# as14120_x31_fpga_power_conf.net
KiCad netlist of a schematic drawn in Altium Designer
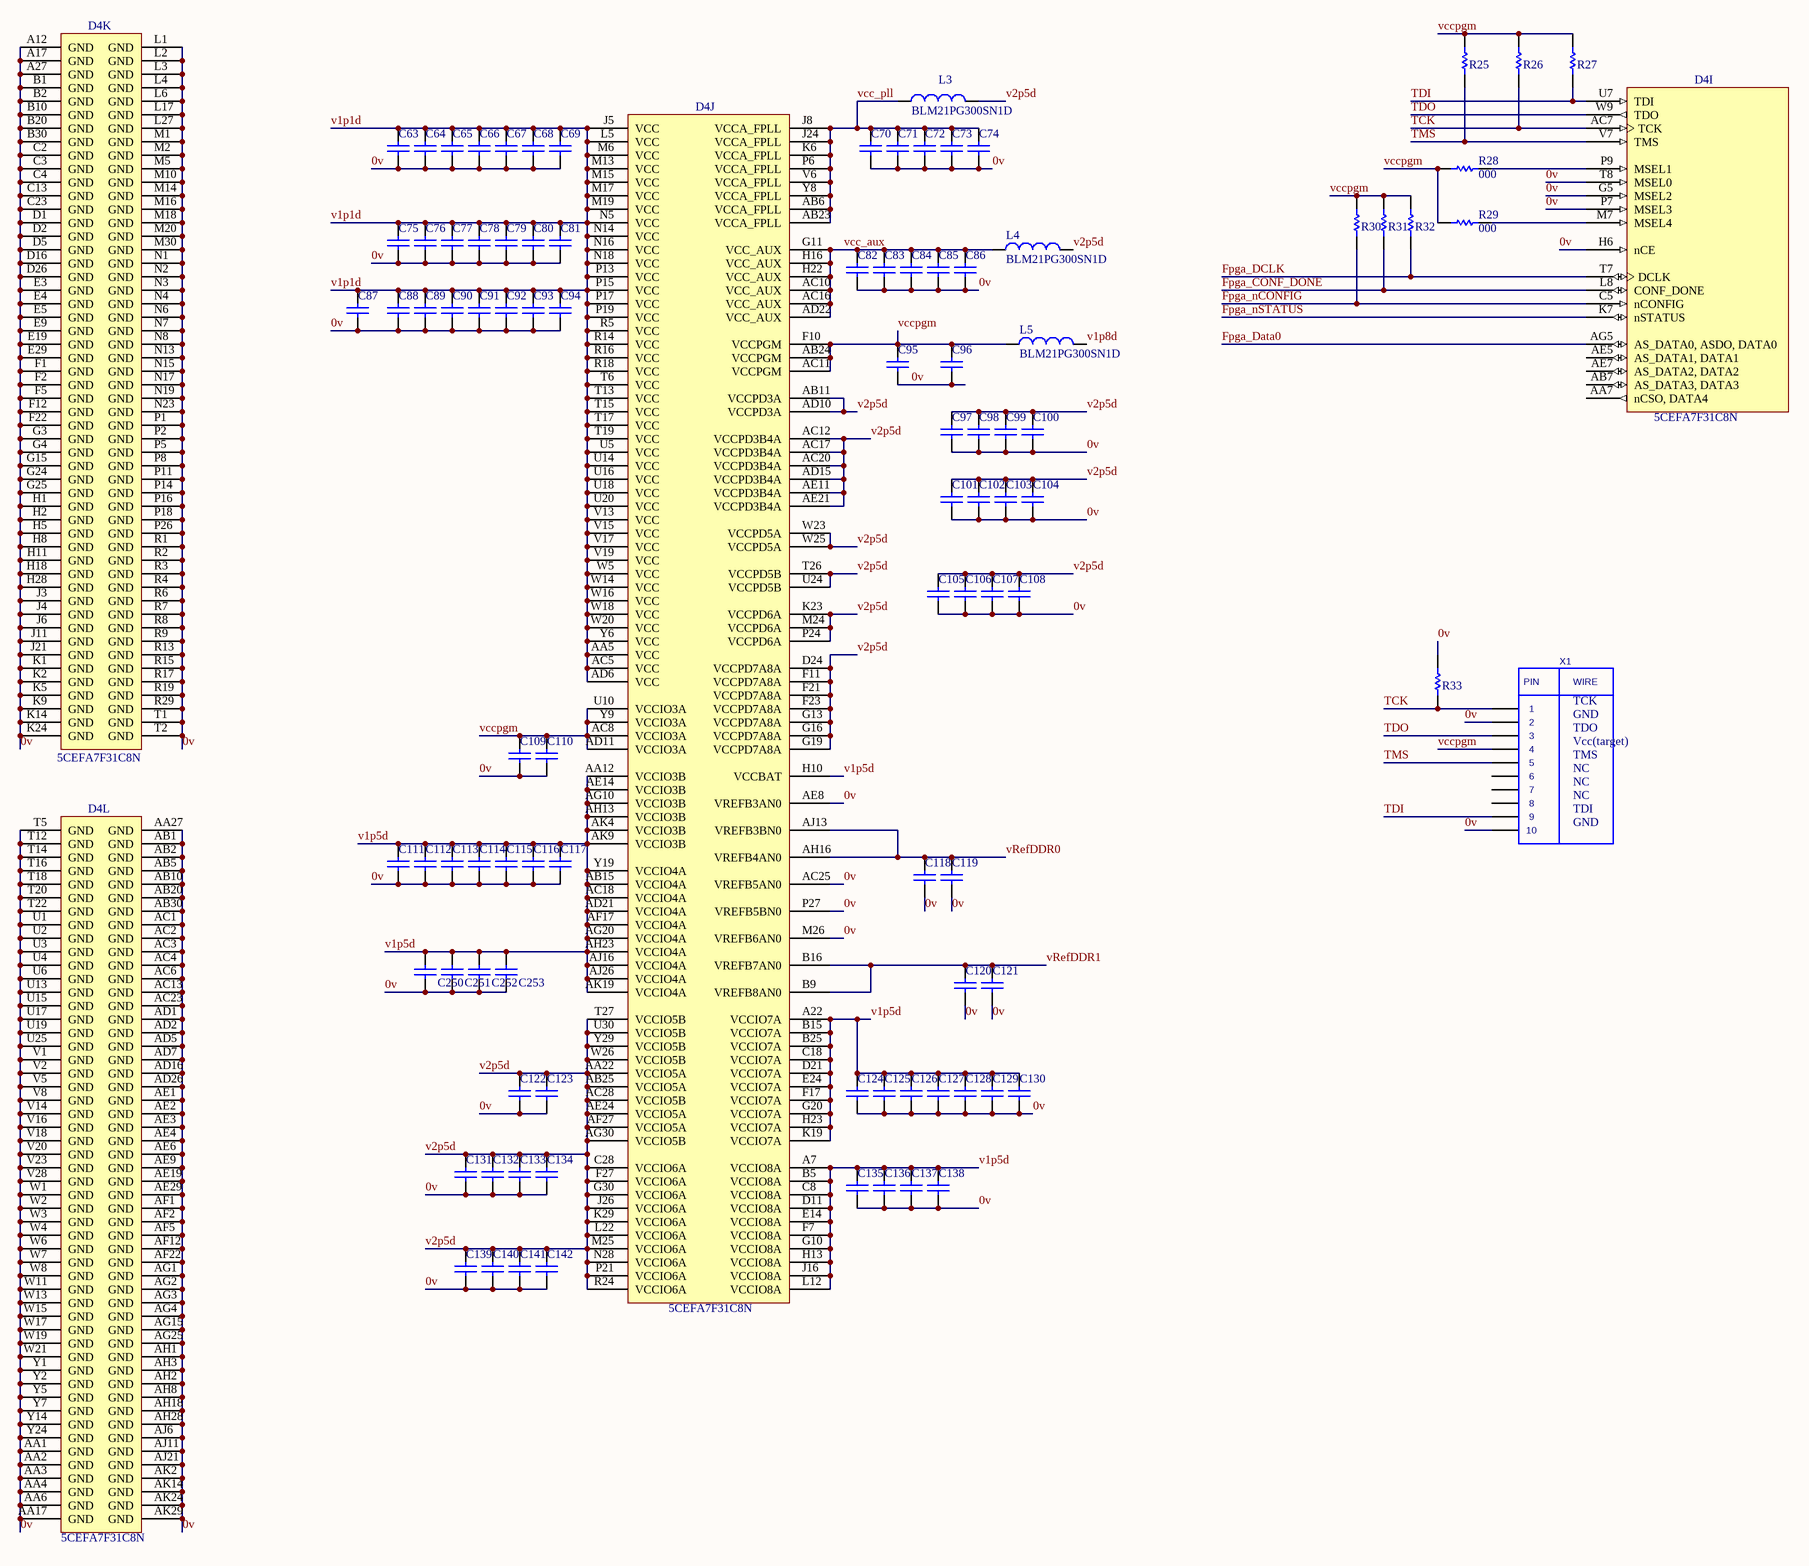
[diagram p0: as14120_x31_fpga_power_conf.SchDoc]

(export (version "E")
  (design (tool "Eeschema 10.0.6"))
  (components
    (comp (ref "C63")
      (value "CAP 1uF 10V 0402(1005)")
      (footprint "CAPC0402(1005)60_M")
      (description "CAP 1uF 10V ±20% 0402 (1005 Metric) Thickness 0.6mm SMD")
      (fields (field (name "TOLERANCE") "±20%"))
      (libsource (lib "as14120") (part "CAP_0402"))
    )
    (comp (ref "C64")
      (value "CAP 1uF 10V 0402(1005)")
      (footprint "CAPC0402(1005)60_M")
      (description "CAP 1uF 10V ±20% 0402 (1005 Metric) Thickness 0.6mm SMD")
      (fields (field (name "TOLERANCE") "±20%"))
      (libsource (lib "as14120") (part "CAP_0402"))
    )
    (comp (ref "C65")
      (value "CAP 1uF 10V 0402(1005)")
      (footprint "CAPC0402(1005)60_M")
      (description "CAP 1uF 10V ±20% 0402 (1005 Metric) Thickness 0.6mm SMD")
      (fields (field (name "TOLERANCE") "±20%"))
      (libsource (lib "as14120") (part "CAP_0402"))
    )
    (comp (ref "C66")
      (value "CAP 1uF 10V 0402(1005)")
      (footprint "CAPC0402(1005)60_M")
      (description "CAP 1uF 10V ±20% 0402 (1005 Metric) Thickness 0.6mm SMD")
      (fields (field (name "TOLERANCE") "±20%"))
      (libsource (lib "as14120") (part "CAP_0402"))
    )
    (comp (ref "C67")
      (value "CAP 1uF 10V 0402(1005)")
      (footprint "CAPC0402(1005)60_M")
      (description "CAP 1uF 10V ±20% 0402 (1005 Metric) Thickness 0.6mm SMD")
      (fields (field (name "TOLERANCE") "±20%"))
      (libsource (lib "as14120") (part "CAP_0402"))
    )
    (comp (ref "C68")
      (value "CAP 1uF 10V 0402(1005)")
      (footprint "CAPC0402(1005)60_M")
      (description "CAP 1uF 10V ±20% 0402 (1005 Metric) Thickness 0.6mm SMD")
      (fields (field (name "TOLERANCE") "±20%"))
      (libsource (lib "as14120") (part "CAP_0402"))
    )
    (comp (ref "C69")
      (value "CAP 1uF 10V 0402(1005)")
      (footprint "CAPC0402(1005)60_M")
      (description "CAP 1uF 10V ±20% 0402 (1005 Metric) Thickness 0.6mm SMD")
      (fields (field (name "TOLERANCE") "±20%"))
      (libsource (lib "as14120") (part "CAP_0402"))
    )
    (comp (ref "C70")
      (value "CAP 1uF 10V 0402(1005)")
      (footprint "CAPC0402(1005)60_M")
      (description "CAP 1uF 10V ±20% 0402 (1005 Metric) Thickness 0.6mm SMD")
      (fields (field (name "TOLERANCE") "±20%"))
      (libsource (lib "as14120") (part "CAP_0402"))
    )
    (comp (ref "C71")
      (value "CAP 1uF 10V 0402(1005)")
      (footprint "CAPC0402(1005)60_M")
      (description "CAP 1uF 10V ±20% 0402 (1005 Metric) Thickness 0.6mm SMD")
      (fields (field (name "TOLERANCE") "±20%"))
      (libsource (lib "as14120") (part "CAP_0402"))
    )
    (comp (ref "C72")
      (value "CAP 1uF 10V 0402(1005)")
      (footprint "CAPC0402(1005)60_M")
      (description "CAP 1uF 10V ±20% 0402 (1005 Metric) Thickness 0.6mm SMD")
      (fields (field (name "TOLERANCE") "±20%"))
      (libsource (lib "as14120") (part "CAP_0402"))
    )
    (comp (ref "C73")
      (value "CAP 1uF 10V 0402(1005)")
      (footprint "CAPC0402(1005)60_M")
      (description "CAP 1uF 10V ±20% 0402 (1005 Metric) Thickness 0.6mm SMD")
      (fields (field (name "TOLERANCE") "±20%"))
      (libsource (lib "as14120") (part "CAP_0402"))
    )
    (comp (ref "C74")
      (value "CAP 1uF 10V 0402(1005)")
      (footprint "CAPC0402(1005)60_M")
      (description "CAP 1uF 10V ±20% 0402 (1005 Metric) Thickness 0.6mm SMD")
      (fields (field (name "TOLERANCE") "±20%"))
      (libsource (lib "as14120") (part "CAP_0402"))
    )
    (comp (ref "C75")
      (value "CAP 1uF 10V 0402(1005)")
      (footprint "CAPC0402(1005)60_M")
      (description "CAP 1uF 10V ±20% 0402 (1005 Metric) Thickness 0.6mm SMD")
      (fields (field (name "TOLERANCE") "±20%"))
      (libsource (lib "as14120") (part "CAP_0402"))
    )
    (comp (ref "C76")
      (value "CAP 1uF 10V 0402(1005)")
      (footprint "CAPC0402(1005)60_M")
      (description "CAP 1uF 10V ±20% 0402 (1005 Metric) Thickness 0.6mm SMD")
      (fields (field (name "TOLERANCE") "±20%"))
      (libsource (lib "as14120") (part "CAP_0402"))
    )
    (comp (ref "C77")
      (value "CAP 1uF 10V 0402(1005)")
      (footprint "CAPC0402(1005)60_M")
      (description "CAP 1uF 10V ±20% 0402 (1005 Metric) Thickness 0.6mm SMD")
      (fields (field (name "TOLERANCE") "±20%"))
      (libsource (lib "as14120") (part "CAP_0402"))
    )
    (comp (ref "C78")
      (value "CAP 1uF 10V 0402(1005)")
      (footprint "CAPC0402(1005)60_M")
      (description "CAP 1uF 10V ±20% 0402 (1005 Metric) Thickness 0.6mm SMD")
      (fields (field (name "TOLERANCE") "±20%"))
      (libsource (lib "as14120") (part "CAP_0402"))
    )
    (comp (ref "C79")
      (value "CAP 1uF 10V 0402(1005)")
      (footprint "CAPC0402(1005)60_M")
      (description "CAP 1uF 10V ±20% 0402 (1005 Metric) Thickness 0.6mm SMD")
      (fields (field (name "TOLERANCE") "±20%"))
      (libsource (lib "as14120") (part "CAP_0402"))
    )
    (comp (ref "C80")
      (value "CAP 1uF 10V 0402(1005)")
      (footprint "CAPC0402(1005)60_M")
      (description "CAP 1uF 10V ±20% 0402 (1005 Metric) Thickness 0.6mm SMD")
      (fields (field (name "TOLERANCE") "±20%"))
      (libsource (lib "as14120") (part "CAP_0402"))
    )
    (comp (ref "C81")
      (value "CAP 1uF 10V 0402(1005)")
      (footprint "CAPC0402(1005)60_M")
      (description "CAP 1uF 10V ±20% 0402 (1005 Metric) Thickness 0.6mm SMD")
      (fields (field (name "TOLERANCE") "±20%"))
      (libsource (lib "as14120") (part "CAP_0402"))
    )
    (comp (ref "C82")
      (value "CAP 1uF 10V 0402(1005)")
      (footprint "CAPC0402(1005)60_M")
      (description "CAP 1uF 10V ±20% 0402 (1005 Metric) Thickness 0.6mm SMD")
      (fields (field (name "TOLERANCE") "±20%"))
      (libsource (lib "as14120") (part "CAP_0402"))
    )
    (comp (ref "C83")
      (value "CAP 1uF 10V 0402(1005)")
      (footprint "CAPC0402(1005)60_M")
      (description "CAP 1uF 10V ±20% 0402 (1005 Metric) Thickness 0.6mm SMD")
      (fields (field (name "TOLERANCE") "±20%"))
      (libsource (lib "as14120") (part "CAP_0402"))
    )
    (comp (ref "C84")
      (value "CAP 1uF 10V 0402(1005)")
      (footprint "CAPC0402(1005)60_M")
      (description "CAP 1uF 10V ±20% 0402 (1005 Metric) Thickness 0.6mm SMD")
      (fields (field (name "TOLERANCE") "±20%"))
      (libsource (lib "as14120") (part "CAP_0402"))
    )
    (comp (ref "C85")
      (value "CAP 1uF 10V 0402(1005)")
      (footprint "CAPC0402(1005)60_M")
      (description "CAP 1uF 10V ±20% 0402 (1005 Metric) Thickness 0.6mm SMD")
      (fields (field (name "TOLERANCE") "±20%"))
      (libsource (lib "as14120") (part "CAP_0402"))
    )
    (comp (ref "C86")
      (value "CAP 1uF 10V 0402(1005)")
      (footprint "CAPC0402(1005)60_M")
      (description "CAP 1uF 10V ±20% 0402 (1005 Metric) Thickness 0.6mm SMD")
      (fields (field (name "TOLERANCE") "±20%"))
      (libsource (lib "as14120") (part "CAP_0402"))
    )
    (comp (ref "C87")
      (value "CAP 1uF 10V 0402(1005)")
      (footprint "CAPC0402(1005)60_M")
      (description "CAP 1uF 10V ±20% 0402 (1005 Metric) Thickness 0.6mm SMD")
      (fields (field (name "TOLERANCE") "±20%"))
      (libsource (lib "as14120") (part "CAP_0402"))
    )
    (comp (ref "C88")
      (value "CAP 1uF 10V 0402(1005)")
      (footprint "CAPC0402(1005)60_M")
      (description "CAP 1uF 10V ±20% 0402 (1005 Metric) Thickness 0.6mm SMD")
      (fields (field (name "TOLERANCE") "±20%"))
      (libsource (lib "as14120") (part "CAP_0402"))
    )
    (comp (ref "C89")
      (value "CAP 1uF 10V 0402(1005)")
      (footprint "CAPC0402(1005)60_M")
      (description "CAP 1uF 10V ±20% 0402 (1005 Metric) Thickness 0.6mm SMD")
      (fields (field (name "TOLERANCE") "±20%"))
      (libsource (lib "as14120") (part "CAP_0402"))
    )
    (comp (ref "C90")
      (value "CAP 1uF 10V 0402(1005)")
      (footprint "CAPC0402(1005)60_M")
      (description "CAP 1uF 10V ±20% 0402 (1005 Metric) Thickness 0.6mm SMD")
      (fields (field (name "TOLERANCE") "±20%"))
      (libsource (lib "as14120") (part "CAP_0402"))
    )
    (comp (ref "C91")
      (value "CAP 1uF 10V 0402(1005)")
      (footprint "CAPC0402(1005)60_M")
      (description "CAP 1uF 10V ±20% 0402 (1005 Metric) Thickness 0.6mm SMD")
      (fields (field (name "TOLERANCE") "±20%"))
      (libsource (lib "as14120") (part "CAP_0402"))
    )
    (comp (ref "C92")
      (value "CAP 1uF 10V 0402(1005)")
      (footprint "CAPC0402(1005)60_M")
      (description "CAP 1uF 10V ±20% 0402 (1005 Metric) Thickness 0.6mm SMD")
      (fields (field (name "TOLERANCE") "±20%"))
      (libsource (lib "as14120") (part "CAP_0402"))
    )
    (comp (ref "C93")
      (value "CAP 1uF 10V 0402(1005)")
      (footprint "CAPC0402(1005)60_M")
      (description "CAP 1uF 10V ±20% 0402 (1005 Metric) Thickness 0.6mm SMD")
      (fields (field (name "TOLERANCE") "±20%"))
      (libsource (lib "as14120") (part "CAP_0402"))
    )
    (comp (ref "C94")
      (value "CAP 1uF 10V 0402(1005)")
      (footprint "CAPC0402(1005)60_M")
      (description "CAP 1uF 10V ±20% 0402 (1005 Metric) Thickness 0.6mm SMD")
      (fields (field (name "TOLERANCE") "±20%"))
      (libsource (lib "as14120") (part "CAP_0402"))
    )
    (comp (ref "C95")
      (value "CAP 1uF 10V 0402(1005)")
      (footprint "CAPC0402(1005)60_M")
      (description "CAP 1uF 10V ±20% 0402 (1005 Metric) Thickness 0.6mm SMD")
      (fields (field (name "TOLERANCE") "±20%"))
      (libsource (lib "as14120") (part "CAP_0402"))
    )
    (comp (ref "C96")
      (value "CAP 1uF 10V 0402(1005)")
      (footprint "CAPC0402(1005)60_M")
      (description "CAP 1uF 10V ±20% 0402 (1005 Metric) Thickness 0.6mm SMD")
      (fields (field (name "TOLERANCE") "±20%"))
      (libsource (lib "as14120") (part "CAP_0402"))
    )
    (comp (ref "C97")
      (value "CAP 1uF 10V 0402(1005)")
      (footprint "CAPC0402(1005)60_M")
      (description "CAP 1uF 10V ±20% 0402 (1005 Metric) Thickness 0.6mm SMD")
      (fields (field (name "TOLERANCE") "±20%"))
      (libsource (lib "as14120") (part "CAP_0402"))
    )
    (comp (ref "C98")
      (value "CAP 1uF 10V 0402(1005)")
      (footprint "CAPC0402(1005)60_M")
      (description "CAP 1uF 10V ±20% 0402 (1005 Metric) Thickness 0.6mm SMD")
      (fields (field (name "TOLERANCE") "±20%"))
      (libsource (lib "as14120") (part "CAP_0402"))
    )
    (comp (ref "C99")
      (value "CAP 1uF 10V 0402(1005)")
      (footprint "CAPC0402(1005)60_M")
      (description "CAP 1uF 10V ±20% 0402 (1005 Metric) Thickness 0.6mm SMD")
      (fields (field (name "TOLERANCE") "±20%"))
      (libsource (lib "as14120") (part "CAP_0402"))
    )
    (comp (ref "C100")
      (value "CAP 1uF 10V 0402(1005)")
      (footprint "CAPC0402(1005)60_M")
      (description "CAP 1uF 10V ±20% 0402 (1005 Metric) Thickness 0.6mm SMD")
      (fields (field (name "TOLERANCE") "±20%"))
      (libsource (lib "as14120") (part "CAP_0402"))
    )
    (comp (ref "C101")
      (value "CAP 1uF 10V 0402(1005)")
      (footprint "CAPC0402(1005)60_M")
      (description "CAP 1uF 10V ±20% 0402 (1005 Metric) Thickness 0.6mm SMD")
      (fields (field (name "TOLERANCE") "±20%"))
      (libsource (lib "as14120") (part "CAP_0402"))
    )
    (comp (ref "C102")
      (value "CAP 1uF 10V 0402(1005)")
      (footprint "CAPC0402(1005)60_M")
      (description "CAP 1uF 10V ±20% 0402 (1005 Metric) Thickness 0.6mm SMD")
      (fields (field (name "TOLERANCE") "±20%"))
      (libsource (lib "as14120") (part "CAP_0402"))
    )
    (comp (ref "C103")
      (value "CAP 1uF 10V 0402(1005)")
      (footprint "CAPC0402(1005)60_M")
      (description "CAP 1uF 10V ±20% 0402 (1005 Metric) Thickness 0.6mm SMD")
      (fields (field (name "TOLERANCE") "±20%"))
      (libsource (lib "as14120") (part "CAP_0402"))
    )
    (comp (ref "C104")
      (value "CAP 1uF 10V 0402(1005)")
      (footprint "CAPC0402(1005)60_M")
      (description "CAP 1uF 10V ±20% 0402 (1005 Metric) Thickness 0.6mm SMD")
      (fields (field (name "TOLERANCE") "±20%"))
      (libsource (lib "as14120") (part "CAP_0402"))
    )
    (comp (ref "C105")
      (value "CAP 1uF 10V 0402(1005)")
      (footprint "CAPC0402(1005)60_M")
      (description "CAP 1uF 10V ±20% 0402 (1005 Metric) Thickness 0.6mm SMD")
      (fields (field (name "TOLERANCE") "±20%"))
      (libsource (lib "as14120") (part "CAP_0402"))
    )
    (comp (ref "C106")
      (value "CAP 1uF 10V 0402(1005)")
      (footprint "CAPC0402(1005)60_M")
      (description "CAP 1uF 10V ±20% 0402 (1005 Metric) Thickness 0.6mm SMD")
      (fields (field (name "TOLERANCE") "±20%"))
      (libsource (lib "as14120") (part "CAP_0402"))
    )
    (comp (ref "C107")
      (value "CAP 1uF 10V 0402(1005)")
      (footprint "CAPC0402(1005)60_M")
      (description "CAP 1uF 10V ±20% 0402 (1005 Metric) Thickness 0.6mm SMD")
      (fields (field (name "TOLERANCE") "±20%"))
      (libsource (lib "as14120") (part "CAP_0402"))
    )
    (comp (ref "C108")
      (value "CAP 1uF 10V 0402(1005)")
      (footprint "CAPC0402(1005)60_M")
      (description "CAP 1uF 10V ±20% 0402 (1005 Metric) Thickness 0.6mm SMD")
      (fields (field (name "TOLERANCE") "±20%"))
      (libsource (lib "as14120") (part "CAP_0402"))
    )
    (comp (ref "C109")
      (value "CAP 1uF 10V 0402(1005)")
      (footprint "CAPC0402(1005)60_M")
      (description "CAP 1uF 10V ±20% 0402 (1005 Metric) Thickness 0.6mm SMD")
      (fields (field (name "TOLERANCE") "±20%"))
      (libsource (lib "as14120") (part "CAP_0402"))
    )
    (comp (ref "C110")
      (value "CAP 1uF 10V 0402(1005)")
      (footprint "CAPC0402(1005)60_M")
      (description "CAP 1uF 10V ±20% 0402 (1005 Metric) Thickness 0.6mm SMD")
      (fields (field (name "TOLERANCE") "±20%"))
      (libsource (lib "as14120") (part "CAP_0402"))
    )
    (comp (ref "C111")
      (value "CAP 1uF 10V 0402(1005)")
      (footprint "CAPC0402(1005)60_M")
      (description "CAP 1uF 10V ±20% 0402 (1005 Metric) Thickness 0.6mm SMD")
      (fields (field (name "TOLERANCE") "±20%"))
      (libsource (lib "as14120") (part "CAP_0402"))
    )
    (comp (ref "C112")
      (value "CAP 1uF 10V 0402(1005)")
      (footprint "CAPC0402(1005)60_M")
      (description "CAP 1uF 10V ±20% 0402 (1005 Metric) Thickness 0.6mm SMD")
      (fields (field (name "TOLERANCE") "±20%"))
      (libsource (lib "as14120") (part "CAP_0402"))
    )
    (comp (ref "C113")
      (value "CAP 1uF 10V 0402(1005)")
      (footprint "CAPC0402(1005)60_M")
      (description "CAP 1uF 10V ±20% 0402 (1005 Metric) Thickness 0.6mm SMD")
      (fields (field (name "TOLERANCE") "±20%"))
      (libsource (lib "as14120") (part "CAP_0402"))
    )
    (comp (ref "C114")
      (value "CAP 1uF 10V 0402(1005)")
      (footprint "CAPC0402(1005)60_M")
      (description "CAP 1uF 10V ±20% 0402 (1005 Metric) Thickness 0.6mm SMD")
      (fields (field (name "TOLERANCE") "±20%"))
      (libsource (lib "as14120") (part "CAP_0402"))
    )
    (comp (ref "C115")
      (value "CAP 1uF 10V 0402(1005)")
      (footprint "CAPC0402(1005)60_M")
      (description "CAP 1uF 10V ±20% 0402 (1005 Metric) Thickness 0.6mm SMD")
      (fields (field (name "TOLERANCE") "±20%"))
      (libsource (lib "as14120") (part "CAP_0402"))
    )
    (comp (ref "C116")
      (value "CAP 1uF 10V 0402(1005)")
      (footprint "CAPC0402(1005)60_M")
      (description "CAP 1uF 10V ±20% 0402 (1005 Metric) Thickness 0.6mm SMD")
      (fields (field (name "TOLERANCE") "±20%"))
      (libsource (lib "as14120") (part "CAP_0402"))
    )
    (comp (ref "C117")
      (value "CAP 1uF 10V 0402(1005)")
      (footprint "CAPC0402(1005)60_M")
      (description "CAP 1uF 10V ±20% 0402 (1005 Metric) Thickness 0.6mm SMD")
      (fields (field (name "TOLERANCE") "±20%"))
      (libsource (lib "as14120") (part "CAP_0402"))
    )
    (comp (ref "C118")
      (value "CAP 1uF 10V 0402(1005)")
      (footprint "CAPC0402(1005)60_M")
      (description "CAP 1uF 10V ±20% 0402 (1005 Metric) Thickness 0.6mm SMD")
      (fields (field (name "TOLERANCE") "±20%"))
      (libsource (lib "as14120") (part "CAP_0402"))
    )
    (comp (ref "C119")
      (value "CAP 1uF 10V 0402(1005)")
      (footprint "CAPC0402(1005)60_M")
      (description "CAP 1uF 10V ±20% 0402 (1005 Metric) Thickness 0.6mm SMD")
      (fields (field (name "TOLERANCE") "±20%"))
      (libsource (lib "as14120") (part "CAP_0402"))
    )
    (comp (ref "C120")
      (value "CAP 1uF 10V 0402(1005)")
      (footprint "CAPC0402(1005)60_M")
      (description "CAP 1uF 10V ±20% 0402 (1005 Metric) Thickness 0.6mm SMD")
      (fields (field (name "TOLERANCE") "±20%"))
      (libsource (lib "as14120") (part "CAP_0402"))
    )
    (comp (ref "C121")
      (value "CAP 1uF 10V 0402(1005)")
      (footprint "CAPC0402(1005)60_M")
      (description "CAP 1uF 10V ±20% 0402 (1005 Metric) Thickness 0.6mm SMD")
      (fields (field (name "TOLERANCE") "±20%"))
      (libsource (lib "as14120") (part "CAP_0402"))
    )
    (comp (ref "C122")
      (value "CAP 1uF 10V 0402(1005)")
      (footprint "CAPC0402(1005)60_M")
      (description "CAP 1uF 10V ±20% 0402 (1005 Metric) Thickness 0.6mm SMD")
      (fields (field (name "TOLERANCE") "±20%"))
      (libsource (lib "as14120") (part "CAP_0402"))
    )
    (comp (ref "C123")
      (value "CAP 1uF 10V 0402(1005)")
      (footprint "CAPC0402(1005)60_M")
      (description "CAP 1uF 10V ±20% 0402 (1005 Metric) Thickness 0.6mm SMD")
      (fields (field (name "TOLERANCE") "±20%"))
      (libsource (lib "as14120") (part "CAP_0402"))
    )
    (comp (ref "C124")
      (value "CAP 1uF 10V 0402(1005)")
      (footprint "CAPC0402(1005)60_M")
      (description "CAP 1uF 10V ±20% 0402 (1005 Metric) Thickness 0.6mm SMD")
      (fields (field (name "TOLERANCE") "±20%"))
      (libsource (lib "as14120") (part "CAP_0402"))
    )
    (comp (ref "C125")
      (value "CAP 1uF 10V 0402(1005)")
      (footprint "CAPC0402(1005)60_M")
      (description "CAP 1uF 10V ±20% 0402 (1005 Metric) Thickness 0.6mm SMD")
      (fields (field (name "TOLERANCE") "±20%"))
      (libsource (lib "as14120") (part "CAP_0402"))
    )
    (comp (ref "C126")
      (value "CAP 1uF 10V 0402(1005)")
      (footprint "CAPC0402(1005)60_M")
      (description "CAP 1uF 10V ±20% 0402 (1005 Metric) Thickness 0.6mm SMD")
      (fields (field (name "TOLERANCE") "±20%"))
      (libsource (lib "as14120") (part "CAP_0402"))
    )
    (comp (ref "C127")
      (value "CAP 1uF 10V 0402(1005)")
      (footprint "CAPC0402(1005)60_M")
      (description "CAP 1uF 10V ±20% 0402 (1005 Metric) Thickness 0.6mm SMD")
      (fields (field (name "TOLERANCE") "±20%"))
      (libsource (lib "as14120") (part "CAP_0402"))
    )
    (comp (ref "C128")
      (value "CAP 1uF 10V 0402(1005)")
      (footprint "CAPC0402(1005)60_M")
      (description "CAP 1uF 10V ±20% 0402 (1005 Metric) Thickness 0.6mm SMD")
      (fields (field (name "TOLERANCE") "±20%"))
      (libsource (lib "as14120") (part "CAP_0402"))
    )
    (comp (ref "C129")
      (value "CAP 1uF 10V 0402(1005)")
      (footprint "CAPC0402(1005)60_M")
      (description "CAP 1uF 10V ±20% 0402 (1005 Metric) Thickness 0.6mm SMD")
      (fields (field (name "TOLERANCE") "±20%"))
      (libsource (lib "as14120") (part "CAP_0402"))
    )
    (comp (ref "C130")
      (value "CAP 1uF 10V 0402(1005)")
      (footprint "CAPC0402(1005)60_M")
      (description "CAP 1uF 10V ±20% 0402 (1005 Metric) Thickness 0.6mm SMD")
      (fields (field (name "TOLERANCE") "±20%"))
      (libsource (lib "as14120") (part "CAP_0402"))
    )
    (comp (ref "C131")
      (value "CAP 1uF 10V 0402(1005)")
      (footprint "CAPC0402(1005)60_M")
      (description "CAP 1uF 10V ±20% 0402 (1005 Metric) Thickness 0.6mm SMD")
      (fields (field (name "TOLERANCE") "±20%"))
      (libsource (lib "as14120") (part "CAP_0402"))
    )
    (comp (ref "C132")
      (value "CAP 1uF 10V 0402(1005)")
      (footprint "CAPC0402(1005)60_M")
      (description "CAP 1uF 10V ±20% 0402 (1005 Metric) Thickness 0.6mm SMD")
      (fields (field (name "TOLERANCE") "±20%"))
      (libsource (lib "as14120") (part "CAP_0402"))
    )
    (comp (ref "C133")
      (value "CAP 1uF 10V 0402(1005)")
      (footprint "CAPC0402(1005)60_M")
      (description "CAP 1uF 10V ±20% 0402 (1005 Metric) Thickness 0.6mm SMD")
      (fields (field (name "TOLERANCE") "±20%"))
      (libsource (lib "as14120") (part "CAP_0402"))
    )
    (comp (ref "C134")
      (value "CAP 1uF 10V 0402(1005)")
      (footprint "CAPC0402(1005)60_M")
      (description "CAP 1uF 10V ±20% 0402 (1005 Metric) Thickness 0.6mm SMD")
      (fields (field (name "TOLERANCE") "±20%"))
      (libsource (lib "as14120") (part "CAP_0402"))
    )
    (comp (ref "C135")
      (value "CAP 1uF 10V 0402(1005)")
      (footprint "CAPC0402(1005)60_M")
      (description "CAP 1uF 10V ±20% 0402 (1005 Metric) Thickness 0.6mm SMD")
      (fields (field (name "TOLERANCE") "±20%"))
      (libsource (lib "as14120") (part "CAP_0402"))
    )
    (comp (ref "C136")
      (value "CAP 1uF 10V 0402(1005)")
      (footprint "CAPC0402(1005)60_M")
      (description "CAP 1uF 10V ±20% 0402 (1005 Metric) Thickness 0.6mm SMD")
      (fields (field (name "TOLERANCE") "±20%"))
      (libsource (lib "as14120") (part "CAP_0402"))
    )
    (comp (ref "C137")
      (value "CAP 1uF 10V 0402(1005)")
      (footprint "CAPC0402(1005)60_M")
      (description "CAP 1uF 10V ±20% 0402 (1005 Metric) Thickness 0.6mm SMD")
      (fields (field (name "TOLERANCE") "±20%"))
      (libsource (lib "as14120") (part "CAP_0402"))
    )
    (comp (ref "C138")
      (value "CAP 1uF 10V 0402(1005)")
      (footprint "CAPC0402(1005)60_M")
      (description "CAP 1uF 10V ±20% 0402 (1005 Metric) Thickness 0.6mm SMD")
      (fields (field (name "TOLERANCE") "±20%"))
      (libsource (lib "as14120") (part "CAP_0402"))
    )
    (comp (ref "C139")
      (value "CAP 1uF 10V 0402(1005)")
      (footprint "CAPC0402(1005)60_M")
      (description "CAP 1uF 10V ±20% 0402 (1005 Metric) Thickness 0.6mm SMD")
      (fields (field (name "TOLERANCE") "±20%"))
      (libsource (lib "as14120") (part "CAP_0402"))
    )
    (comp (ref "C140")
      (value "CAP 1uF 10V 0402(1005)")
      (footprint "CAPC0402(1005)60_M")
      (description "CAP 1uF 10V ±20% 0402 (1005 Metric) Thickness 0.6mm SMD")
      (fields (field (name "TOLERANCE") "±20%"))
      (libsource (lib "as14120") (part "CAP_0402"))
    )
    (comp (ref "C141")
      (value "CAP 1uF 10V 0402(1005)")
      (footprint "CAPC0402(1005)60_M")
      (description "CAP 1uF 10V ±20% 0402 (1005 Metric) Thickness 0.6mm SMD")
      (fields (field (name "TOLERANCE") "±20%"))
      (libsource (lib "as14120") (part "CAP_0402"))
    )
    (comp (ref "C142")
      (value "CAP 1uF 10V 0402(1005)")
      (footprint "CAPC0402(1005)60_M")
      (description "CAP 1uF 10V ±20% 0402 (1005 Metric) Thickness 0.6mm SMD")
      (fields (field (name "TOLERANCE") "±20%"))
      (libsource (lib "as14120") (part "CAP_0402"))
    )
    (comp (ref "C250")
      (value "CAP 1uF 10V 0402(1005)")
      (footprint "CAPC0402(1005)60_M")
      (description "CAP 1uF 10V ±20% 0402 (1005 Metric) Thickness 0.6mm SMD")
      (fields (field (name "TOLERANCE") "±20%"))
      (libsource (lib "as14120") (part "CAP_0402"))
    )
    (comp (ref "C251")
      (value "CAP 1uF 10V 0402(1005)")
      (footprint "CAPC0402(1005)60_M")
      (description "CAP 1uF 10V ±20% 0402 (1005 Metric) Thickness 0.6mm SMD")
      (fields (field (name "TOLERANCE") "±20%"))
      (libsource (lib "as14120") (part "CAP_0402"))
    )
    (comp (ref "C252")
      (value "CAP 1uF 10V 0402(1005)")
      (footprint "CAPC0402(1005)60_M")
      (description "CAP 1uF 10V ±20% 0402 (1005 Metric) Thickness 0.6mm SMD")
      (fields (field (name "TOLERANCE") "±20%"))
      (libsource (lib "as14120") (part "CAP_0402"))
    )
    (comp (ref "C253")
      (value "CAP 1uF 10V 0402(1005)")
      (footprint "CAPC0402(1005)60_M")
      (description "CAP 1uF 10V ±20% 0402 (1005 Metric) Thickness 0.6mm SMD")
      (fields (field (name "TOLERANCE") "±20%"))
      (libsource (lib "as14120") (part "CAP_0402"))
    )
    (comp (ref "D4")
      (value "5CEFA7F31C8N")
      (footprint "ALTR-896-FBGA-2000A")
      (fields (field (name "MANUFACTURER") "Altera"))
      (libsource (lib "Altera Cyclone V E") (part "5CEFA7F31C8N"))
    )
    (comp (ref "L3")
      (value "BLM21PG300SN1D")
      (footprint "CAPC0805(2012)100_N")
      (libsource (lib "as14120") (part "Ferrite_beat"))
    )
    (comp (ref "L4")
      (value "BLM21PG300SN1D")
      (footprint "CAPC0805(2012)100_N")
      (libsource (lib "as14120") (part "Ferrite_beat"))
    )
    (comp (ref "L5")
      (value "BLM21PG300SN1D")
      (footprint "CAPC0805(2012)100_N")
      (libsource (lib "as14120") (part "Ferrite_beat"))
    )
    (comp (ref "R25")
      (value "1K 5% 0603(1608)")
      (footprint "RESC0603(1608)_L")
      (description "1K 0.1W 5% 0603 (1608 Metric)  SMD")
      (fields (field (name "TOLERANCE") "5 %") (field (name "POWER") "0.1 W"))
      (libsource (lib "as14120") (part "RES_0603"))
    )
    (comp (ref "R26")
      (value "1K 5% 0603(1608)")
      (footprint "RESC0603(1608)_L")
      (description "1K 0.1W 5% 0603 (1608 Metric)  SMD")
      (fields (field (name "TOLERANCE") "5 %") (field (name "POWER") "0.1 W"))
      (libsource (lib "as14120") (part "RES_0603"))
    )
    (comp (ref "R27")
      (value "1K 5% 0603(1608)")
      (footprint "RESC0603(1608)_L")
      (description "1K 0.1W 5% 0603 (1608 Metric)  SMD")
      (fields (field (name "TOLERANCE") "5 %") (field (name "POWER") "0.1 W"))
      (libsource (lib "as14120") (part "RES_0603"))
    )
    (comp (ref "R28")
      (value "000")
      (footprint "RESC0603(1608)_L")
      (description "1K 0.1W 5% 0603 (1608 Metric)  SMD")
      (fields (field (name "TOLERANCE") "5 %") (field (name "POWER") "0.1 W"))
      (libsource (lib "as14120") (part "RES_0603"))
    )
    (comp (ref "R29")
      (value "000")
      (footprint "RESC0603(1608)_L")
      (description "1K 0.1W 5% 0603 (1608 Metric)  SMD")
      (fields (field (name "TOLERANCE") "5 %") (field (name "POWER") "0.1 W"))
      (libsource (lib "as14120") (part "RES_0603"))
    )
    (comp (ref "R30")
      (value "1K 5% 0603(1608)")
      (footprint "RESC0603(1608)_L")
      (description "1K 0.1W 5% 0603 (1608 Metric)  SMD")
      (fields (field (name "TOLERANCE") "5 %") (field (name "POWER") "0.1 W"))
      (libsource (lib "as14120") (part "RES_0603"))
    )
    (comp (ref "R31")
      (value "1K 5% 0603(1608)")
      (footprint "RESC0603(1608)_L")
      (description "1K 0.1W 5% 0603 (1608 Metric)  SMD")
      (fields (field (name "TOLERANCE") "5 %") (field (name "POWER") "0.1 W"))
      (libsource (lib "as14120") (part "RES_0603"))
    )
    (comp (ref "R32")
      (value "1K 5% 0603(1608)")
      (footprint "RESC0603(1608)_L")
      (description "1K 0.1W 5% 0603 (1608 Metric)  SMD")
      (fields (field (name "TOLERANCE") "5 %") (field (name "POWER") "0.1 W"))
      (libsource (lib "as14120") (part "RES_0603"))
    )
    (comp (ref "R33")
      (value "1K 5% 0603(1608)")
      (footprint "RESC0603(1608)_L")
      (description "1K 0.1W 5% 0603 (1608 Metric)  SMD")
      (fields (field (name "TOLERANCE") "5 %") (field (name "POWER") "0.1 W"))
      (libsource (lib "as14120") (part "RES_0603"))
    )
    (comp (ref "X1") (value "IDC10") (footprint "IDC10M") (libsource (lib "alexsb") (part "IDC10")))
  )
  (nets
    (net (code "1") (name "/0v") (class "Default")
      (node (ref "C100") (pin "1") (pinfunction "1_1") (pintype "passive"))
      (node (ref "C101") (pin "1") (pinfunction "1_1") (pintype "passive"))
      (node (ref "C102") (pin "1") (pinfunction "1_1") (pintype "passive"))
      (node (ref "C103") (pin "1") (pinfunction "1_1") (pintype "passive"))
      (node (ref "C104") (pin "1") (pinfunction "1_1") (pintype "passive"))
      (node (ref "C105") (pin "1") (pinfunction "1_1") (pintype "passive"))
      (node (ref "C106") (pin "1") (pinfunction "1_1") (pintype "passive"))
      (node (ref "C107") (pin "1") (pinfunction "1_1") (pintype "passive"))
      (node (ref "C108") (pin "1") (pinfunction "1_1") (pintype "passive"))
      (node (ref "C109") (pin "1") (pinfunction "1_1") (pintype "passive"))
      (node (ref "C110") (pin "1") (pinfunction "1_1") (pintype "passive"))
      (node (ref "C111") (pin "1") (pinfunction "1_1") (pintype "passive"))
      (node (ref "C112") (pin "1") (pinfunction "1_1") (pintype "passive"))
      (node (ref "C113") (pin "1") (pinfunction "1_1") (pintype "passive"))
      (node (ref "C114") (pin "1") (pinfunction "1_1") (pintype "passive"))
      (node (ref "C115") (pin "1") (pinfunction "1_1") (pintype "passive"))
      (node (ref "C116") (pin "1") (pinfunction "1_1") (pintype "passive"))
      (node (ref "C117") (pin "1") (pinfunction "1_1") (pintype "passive"))
      (node (ref "C118") (pin "1") (pinfunction "1_1") (pintype "passive"))
      (node (ref "C119") (pin "1") (pinfunction "1_1") (pintype "passive"))
      (node (ref "C120") (pin "1") (pinfunction "1_1") (pintype "passive"))
      (node (ref "C121") (pin "1") (pinfunction "1_1") (pintype "passive"))
      (node (ref "C122") (pin "1") (pinfunction "1_1") (pintype "passive"))
      (node (ref "C123") (pin "1") (pinfunction "1_1") (pintype "passive"))
      (node (ref "C124") (pin "1") (pinfunction "1_1") (pintype "passive"))
      (node (ref "C125") (pin "1") (pinfunction "1_1") (pintype "passive"))
      (node (ref "C126") (pin "1") (pinfunction "1_1") (pintype "passive"))
      (node (ref "C127") (pin "1") (pinfunction "1_1") (pintype "passive"))
      (node (ref "C128") (pin "1") (pinfunction "1_1") (pintype "passive"))
      (node (ref "C129") (pin "1") (pinfunction "1_1") (pintype "passive"))
      (node (ref "C130") (pin "1") (pinfunction "1_1") (pintype "passive"))
      (node (ref "C131") (pin "1") (pinfunction "1_1") (pintype "passive"))
      (node (ref "C132") (pin "1") (pinfunction "1_1") (pintype "passive"))
      (node (ref "C133") (pin "1") (pinfunction "1_1") (pintype "passive"))
      (node (ref "C134") (pin "1") (pinfunction "1_1") (pintype "passive"))
      (node (ref "C135") (pin "1") (pinfunction "1_1") (pintype "passive"))
      (node (ref "C136") (pin "1") (pinfunction "1_1") (pintype "passive"))
      (node (ref "C137") (pin "1") (pinfunction "1_1") (pintype "passive"))
      (node (ref "C138") (pin "1") (pinfunction "1_1") (pintype "passive"))
      (node (ref "C139") (pin "1") (pinfunction "1_1") (pintype "passive"))
      (node (ref "C140") (pin "1") (pinfunction "1_1") (pintype "passive"))
      (node (ref "C141") (pin "1") (pinfunction "1_1") (pintype "passive"))
      (node (ref "C142") (pin "1") (pinfunction "1_1") (pintype "passive"))
      (node (ref "C250") (pin "1") (pinfunction "1_1") (pintype "passive"))
      (node (ref "C251") (pin "1") (pinfunction "1_1") (pintype "passive"))
      (node (ref "C252") (pin "1") (pinfunction "1_1") (pintype "passive"))
      (node (ref "C253") (pin "1") (pinfunction "1_1") (pintype "passive"))
      (node (ref "C63") (pin "1") (pinfunction "1_1") (pintype "passive"))
      (node (ref "C64") (pin "1") (pinfunction "1_1") (pintype "passive"))
      (node (ref "C65") (pin "1") (pinfunction "1_1") (pintype "passive"))
      (node (ref "C66") (pin "1") (pinfunction "1_1") (pintype "passive"))
      (node (ref "C67") (pin "1") (pinfunction "1_1") (pintype "passive"))
      (node (ref "C68") (pin "1") (pinfunction "1_1") (pintype "passive"))
      (node (ref "C69") (pin "1") (pinfunction "1_1") (pintype "passive"))
      (node (ref "C70") (pin "1") (pinfunction "1_1") (pintype "passive"))
      (node (ref "C71") (pin "1") (pinfunction "1_1") (pintype "passive"))
      (node (ref "C72") (pin "1") (pinfunction "1_1") (pintype "passive"))
      (node (ref "C73") (pin "1") (pinfunction "1_1") (pintype "passive"))
      (node (ref "C74") (pin "1") (pinfunction "1_1") (pintype "passive"))
      (node (ref "C75") (pin "1") (pinfunction "1_1") (pintype "passive"))
      (node (ref "C76") (pin "1") (pinfunction "1_1") (pintype "passive"))
      (node (ref "C77") (pin "1") (pinfunction "1_1") (pintype "passive"))
      (node (ref "C78") (pin "1") (pinfunction "1_1") (pintype "passive"))
      (node (ref "C79") (pin "1") (pinfunction "1_1") (pintype "passive"))
      (node (ref "C80") (pin "1") (pinfunction "1_1") (pintype "passive"))
      (node (ref "C81") (pin "1") (pinfunction "1_1") (pintype "passive"))
      (node (ref "C82") (pin "1") (pinfunction "1_1") (pintype "passive"))
      (node (ref "C83") (pin "1") (pinfunction "1_1") (pintype "passive"))
      (node (ref "C84") (pin "1") (pinfunction "1_1") (pintype "passive"))
      (node (ref "C85") (pin "1") (pinfunction "1_1") (pintype "passive"))
      (node (ref "C86") (pin "1") (pinfunction "1_1") (pintype "passive"))
      (node (ref "C87") (pin "1") (pinfunction "1_1") (pintype "passive"))
      (node (ref "C88") (pin "1") (pinfunction "1_1") (pintype "passive"))
      (node (ref "C89") (pin "1") (pinfunction "1_1") (pintype "passive"))
      (node (ref "C90") (pin "1") (pinfunction "1_1") (pintype "passive"))
      (node (ref "C91") (pin "1") (pinfunction "1_1") (pintype "passive"))
      (node (ref "C92") (pin "1") (pinfunction "1_1") (pintype "passive"))
      (node (ref "C93") (pin "1") (pinfunction "1_1") (pintype "passive"))
      (node (ref "C94") (pin "1") (pinfunction "1_1") (pintype "passive"))
      (node (ref "C95") (pin "1") (pinfunction "1_1") (pintype "passive"))
      (node (ref "C96") (pin "1") (pinfunction "1_1") (pintype "passive"))
      (node (ref "C97") (pin "1") (pinfunction "1_1") (pintype "passive"))
      (node (ref "C98") (pin "1") (pinfunction "1_1") (pintype "passive"))
      (node (ref "C99") (pin "1") (pinfunction "1_1") (pintype "passive"))
      (node (ref "D4") (pin "A12") (pinfunction "GND_A12") (pintype "power_in"))
      (node (ref "D4") (pin "A17") (pinfunction "GND_A17") (pintype "power_in"))
      (node (ref "D4") (pin "A27") (pinfunction "GND_A27") (pintype "power_in"))
      (node (ref "D4") (pin "AA1") (pinfunction "GND_AA1") (pintype "power_in"))
      (node (ref "D4") (pin "AA17") (pinfunction "GND_AA17") (pintype "power_in"))
      (node (ref "D4") (pin "AA2") (pinfunction "GND_AA2") (pintype "power_in"))
      (node (ref "D4") (pin "AA27") (pinfunction "GND_AA27") (pintype "power_in"))
      (node (ref "D4") (pin "AA3") (pinfunction "GND_AA3") (pintype "power_in"))
      (node (ref "D4") (pin "AA4") (pinfunction "GND_AA4") (pintype "power_in"))
      (node (ref "D4") (pin "AA6") (pinfunction "GND_AA6") (pintype "power_in"))
      (node (ref "D4") (pin "AB1") (pinfunction "GND_AB1") (pintype "power_in"))
      (node (ref "D4") (pin "AB10") (pinfunction "GND_AB10") (pintype "power_in"))
      (node (ref "D4") (pin "AB2") (pinfunction "GND_AB2") (pintype "power_in"))
      (node (ref "D4") (pin "AB20") (pinfunction "GND_AB20") (pintype "power_in"))
      (node (ref "D4") (pin "AB30") (pinfunction "GND_AB30") (pintype "power_in"))
      (node (ref "D4") (pin "AB5") (pinfunction "GND_AB5") (pintype "power_in"))
      (node (ref "D4") (pin "AC1") (pinfunction "GND_AC1") (pintype "power_in"))
      (node (ref "D4") (pin "AC13") (pinfunction "GND_AC13") (pintype "power_in"))
      (node (ref "D4") (pin "AC2") (pinfunction "GND_AC2") (pintype "power_in"))
      (node (ref "D4") (pin "AC23") (pinfunction "GND_AC23") (pintype "power_in"))
      (node (ref "D4") (pin "AC25") (pinfunction "VREFB5AN0_AC25") (pintype "power_in"))
      (node (ref "D4") (pin "AC3") (pinfunction "GND_AC3") (pintype "power_in"))
      (node (ref "D4") (pin "AC4") (pinfunction "GND_AC4") (pintype "power_in"))
      (node (ref "D4") (pin "AC6") (pinfunction "GND_AC6") (pintype "power_in"))
      (node (ref "D4") (pin "AD1") (pinfunction "GND_AD1") (pintype "power_in"))
      (node (ref "D4") (pin "AD16") (pinfunction "GND_AD16") (pintype "power_in"))
      (node (ref "D4") (pin "AD2") (pinfunction "GND_AD2") (pintype "power_in"))
      (node (ref "D4") (pin "AD26") (pinfunction "GND_AD26") (pintype "power_in"))
      (node (ref "D4") (pin "AD5") (pinfunction "GND_AD5") (pintype "power_in"))
      (node (ref "D4") (pin "AD7") (pinfunction "GND_AD7") (pintype "power_in"))
      (node (ref "D4") (pin "AE1") (pinfunction "GND_AE1") (pintype "power_in"))
      (node (ref "D4") (pin "AE19") (pinfunction "GND_AE19") (pintype "power_in"))
      (node (ref "D4") (pin "AE2") (pinfunction "GND_AE2") (pintype "power_in"))
      (node (ref "D4") (pin "AE29") (pinfunction "GND_AE29") (pintype "power_in"))
      (node (ref "D4") (pin "AE3") (pinfunction "GND_AE3") (pintype "power_in"))
      (node (ref "D4") (pin "AE4") (pinfunction "GND_AE4") (pintype "power_in"))
      (node (ref "D4") (pin "AE6") (pinfunction "GND_AE6") (pintype "power_in"))
      (node (ref "D4") (pin "AE8") (pinfunction "VREFB3AN0_AE8") (pintype "power_in"))
      (node (ref "D4") (pin "AE9") (pinfunction "GND_AE9") (pintype "power_in"))
      (node (ref "D4") (pin "AF1") (pinfunction "GND_AF1") (pintype "power_in"))
      (node (ref "D4") (pin "AF12") (pinfunction "GND_AF12") (pintype "power_in"))
      (node (ref "D4") (pin "AF2") (pinfunction "GND_AF2") (pintype "power_in"))
      (node (ref "D4") (pin "AF22") (pinfunction "GND_AF22") (pintype "power_in"))
      (node (ref "D4") (pin "AF5") (pinfunction "GND_AF5") (pintype "power_in"))
      (node (ref "D4") (pin "AG1") (pinfunction "GND_AG1") (pintype "power_in"))
      (node (ref "D4") (pin "AG15") (pinfunction "GND_AG15") (pintype "power_in"))
      (node (ref "D4") (pin "AG2") (pinfunction "GND_AG2") (pintype "power_in"))
      (node (ref "D4") (pin "AG25") (pinfunction "GND_AG25") (pintype "power_in"))
      (node (ref "D4") (pin "AG3") (pinfunction "GND_AG3") (pintype "power_in"))
      (node (ref "D4") (pin "AG4") (pinfunction "GND_AG4") (pintype "power_in"))
      (node (ref "D4") (pin "AH1") (pinfunction "GND_AH1") (pintype "power_in"))
      (node (ref "D4") (pin "AH18") (pinfunction "GND_AH18") (pintype "power_in"))
      (node (ref "D4") (pin "AH2") (pinfunction "GND_AH2") (pintype "power_in"))
      (node (ref "D4") (pin "AH28") (pinfunction "GND_AH28") (pintype "power_in"))
      (node (ref "D4") (pin "AH3") (pinfunction "GND_AH3") (pintype "power_in"))
      (node (ref "D4") (pin "AH8") (pinfunction "GND_AH8") (pintype "power_in"))
      (node (ref "D4") (pin "AJ11") (pinfunction "GND_AJ11") (pintype "power_in"))
      (node (ref "D4") (pin "AJ21") (pinfunction "GND_AJ21") (pintype "power_in"))
      (node (ref "D4") (pin "AJ6") (pinfunction "GND_AJ6") (pintype "power_in"))
      (node (ref "D4") (pin "AK14") (pinfunction "GND_AK14") (pintype "power_in"))
      (node (ref "D4") (pin "AK2") (pinfunction "GND_AK2") (pintype "power_in"))
      (node (ref "D4") (pin "AK24") (pinfunction "GND_AK24") (pintype "power_in"))
      (node (ref "D4") (pin "AK29") (pinfunction "GND_AK29") (pintype "power_in"))
      (node (ref "D4") (pin "B1") (pinfunction "GND_B1") (pintype "power_in"))
      (node (ref "D4") (pin "B10") (pinfunction "GND_B10") (pintype "power_in"))
      (node (ref "D4") (pin "B2") (pinfunction "GND_B2") (pintype "power_in"))
      (node (ref "D4") (pin "B20") (pinfunction "GND_B20") (pintype "power_in"))
      (node (ref "D4") (pin "B30") (pinfunction "GND_B30") (pintype "power_in"))
      (node (ref "D4") (pin "C13") (pinfunction "GND_C13") (pintype "power_in"))
      (node (ref "D4") (pin "C2") (pinfunction "GND_C2") (pintype "power_in"))
      (node (ref "D4") (pin "C23") (pinfunction "GND_C23") (pintype "power_in"))
      (node (ref "D4") (pin "C3") (pinfunction "GND_C3") (pintype "power_in"))
      (node (ref "D4") (pin "C4") (pinfunction "GND_C4") (pintype "power_in"))
      (node (ref "D4") (pin "D1") (pinfunction "GND_D1") (pintype "power_in"))
      (node (ref "D4") (pin "D16") (pinfunction "GND_D16") (pintype "power_in"))
      (node (ref "D4") (pin "D2") (pinfunction "GND_D2") (pintype "power_in"))
      (node (ref "D4") (pin "D26") (pinfunction "GND_D26") (pintype "power_in"))
      (node (ref "D4") (pin "D5") (pinfunction "GND_D5") (pintype "power_in"))
      (node (ref "D4") (pin "E19") (pinfunction "GND_E19") (pintype "power_in"))
      (node (ref "D4") (pin "E29") (pinfunction "GND_E29") (pintype "power_in"))
      (node (ref "D4") (pin "E3") (pinfunction "GND_E3") (pintype "power_in"))
      (node (ref "D4") (pin "E4") (pinfunction "GND_E4") (pintype "power_in"))
      (node (ref "D4") (pin "E5") (pinfunction "GND_E5") (pintype "power_in"))
      (node (ref "D4") (pin "E9") (pinfunction "GND_E9") (pintype "power_in"))
      (node (ref "D4") (pin "F1") (pinfunction "GND_F1") (pintype "power_in"))
      (node (ref "D4") (pin "F12") (pinfunction "GND_F12") (pintype "power_in"))
      (node (ref "D4") (pin "F2") (pinfunction "GND_F2") (pintype "power_in"))
      (node (ref "D4") (pin "F22") (pinfunction "GND_F22") (pintype "power_in"))
      (node (ref "D4") (pin "F5") (pinfunction "GND_F5") (pintype "power_in"))
      (node (ref "D4") (pin "G15") (pinfunction "GND_G15") (pintype "power_in"))
      (node (ref "D4") (pin "G24") (pinfunction "GND_G24") (pintype "power_in"))
      (node (ref "D4") (pin "G25") (pinfunction "GND_G25") (pintype "power_in"))
      (node (ref "D4") (pin "G3") (pinfunction "GND_G3") (pintype "power_in"))
      (node (ref "D4") (pin "G4") (pinfunction "GND_G4") (pintype "power_in"))
      (node (ref "D4") (pin "G5") (pinfunction "MSEL2_G5") (pintype "input"))
      (node (ref "D4") (pin "H1") (pinfunction "GND_H1") (pintype "power_in"))
      (node (ref "D4") (pin "H11") (pinfunction "GND_H11") (pintype "power_in"))
      (node (ref "D4") (pin "H18") (pinfunction "GND_H18") (pintype "power_in"))
      (node (ref "D4") (pin "H2") (pinfunction "GND_H2") (pintype "power_in"))
      (node (ref "D4") (pin "H28") (pinfunction "GND_H28") (pintype "power_in"))
      (node (ref "D4") (pin "H5") (pinfunction "GND_H5") (pintype "power_in"))
      (node (ref "D4") (pin "H6") (pinfunction "nCE_H6") (pintype "input"))
      (node (ref "D4") (pin "H8") (pinfunction "GND_H8") (pintype "power_in"))
      (node (ref "D4") (pin "J11") (pinfunction "GND_J11") (pintype "power_in"))
      (node (ref "D4") (pin "J21") (pinfunction "GND_J21") (pintype "power_in"))
      (node (ref "D4") (pin "J3") (pinfunction "GND_J3") (pintype "power_in"))
      (node (ref "D4") (pin "J4") (pinfunction "GND_J4") (pintype "power_in"))
      (node (ref "D4") (pin "J6") (pinfunction "GND_J6") (pintype "power_in"))
      (node (ref "D4") (pin "K1") (pinfunction "GND_K1") (pintype "power_in"))
      (node (ref "D4") (pin "K14") (pinfunction "GND_K14") (pintype "power_in"))
      (node (ref "D4") (pin "K2") (pinfunction "GND_K2") (pintype "power_in"))
      (node (ref "D4") (pin "K24") (pinfunction "GND_K24") (pintype "power_in"))
      (node (ref "D4") (pin "K5") (pinfunction "GND_K5") (pintype "power_in"))
      (node (ref "D4") (pin "K9") (pinfunction "GND_K9") (pintype "power_in"))
      (node (ref "D4") (pin "L1") (pinfunction "GND_L1") (pintype "power_in"))
      (node (ref "D4") (pin "L17") (pinfunction "GND_L17") (pintype "power_in"))
      (node (ref "D4") (pin "L2") (pinfunction "GND_L2") (pintype "power_in"))
      (node (ref "D4") (pin "L27") (pinfunction "GND_L27") (pintype "power_in"))
      (node (ref "D4") (pin "L3") (pinfunction "GND_L3") (pintype "power_in"))
      (node (ref "D4") (pin "L4") (pinfunction "GND_L4") (pintype "power_in"))
      (node (ref "D4") (pin "L6") (pinfunction "GND_L6") (pintype "power_in"))
      (node (ref "D4") (pin "M1") (pinfunction "GND_M1") (pintype "power_in"))
      (node (ref "D4") (pin "M10") (pinfunction "GND_M10") (pintype "power_in"))
      (node (ref "D4") (pin "M14") (pinfunction "GND_M14") (pintype "power_in"))
      (node (ref "D4") (pin "M16") (pinfunction "GND_M16") (pintype "power_in"))
      (node (ref "D4") (pin "M18") (pinfunction "GND_M18") (pintype "power_in"))
      (node (ref "D4") (pin "M2") (pinfunction "GND_M2") (pintype "power_in"))
      (node (ref "D4") (pin "M20") (pinfunction "GND_M20") (pintype "power_in"))
      (node (ref "D4") (pin "M26") (pinfunction "VREFB6AN0_M26") (pintype "power_in"))
      (node (ref "D4") (pin "M30") (pinfunction "GND_M30") (pintype "power_in"))
      (node (ref "D4") (pin "M5") (pinfunction "GND_M5") (pintype "power_in"))
      (node (ref "D4") (pin "N1") (pinfunction "GND_N1") (pintype "power_in"))
      (node (ref "D4") (pin "N13") (pinfunction "GND_N13") (pintype "power_in"))
      (node (ref "D4") (pin "N15") (pinfunction "GND_N15") (pintype "power_in"))
      (node (ref "D4") (pin "N17") (pinfunction "GND_N17") (pintype "power_in"))
      (node (ref "D4") (pin "N19") (pinfunction "GND_N19") (pintype "power_in"))
      (node (ref "D4") (pin "N2") (pinfunction "GND_N2") (pintype "power_in"))
      (node (ref "D4") (pin "N23") (pinfunction "GND_N23") (pintype "power_in"))
      (node (ref "D4") (pin "N3") (pinfunction "GND_N3") (pintype "power_in"))
      (node (ref "D4") (pin "N4") (pinfunction "GND_N4") (pintype "power_in"))
      (node (ref "D4") (pin "N6") (pinfunction "GND_N6") (pintype "power_in"))
      (node (ref "D4") (pin "N7") (pinfunction "GND_N7") (pintype "power_in"))
      (node (ref "D4") (pin "N8") (pinfunction "GND_N8") (pintype "power_in"))
      (node (ref "D4") (pin "P1") (pinfunction "GND_P1") (pintype "power_in"))
      (node (ref "D4") (pin "P11") (pinfunction "GND_P11") (pintype "power_in"))
      (node (ref "D4") (pin "P14") (pinfunction "GND_P14") (pintype "power_in"))
      (node (ref "D4") (pin "P16") (pinfunction "GND_P16") (pintype "power_in"))
      (node (ref "D4") (pin "P18") (pinfunction "GND_P18") (pintype "power_in"))
      (node (ref "D4") (pin "P2") (pinfunction "GND_P2") (pintype "power_in"))
      (node (ref "D4") (pin "P26") (pinfunction "GND_P26") (pintype "power_in"))
      (node (ref "D4") (pin "P27") (pinfunction "VREFB5BN0_P27") (pintype "power_in"))
      (node (ref "D4") (pin "P5") (pinfunction "GND_P5") (pintype "power_in"))
      (node (ref "D4") (pin "P7") (pinfunction "MSEL3_P7") (pintype "input"))
      (node (ref "D4") (pin "P8") (pinfunction "GND_P8") (pintype "power_in"))
      (node (ref "D4") (pin "R1") (pinfunction "GND_R1") (pintype "power_in"))
      (node (ref "D4") (pin "R13") (pinfunction "GND_R13") (pintype "power_in"))
      (node (ref "D4") (pin "R15") (pinfunction "GND_R15") (pintype "power_in"))
      (node (ref "D4") (pin "R17") (pinfunction "GND_R17") (pintype "power_in"))
      (node (ref "D4") (pin "R19") (pinfunction "GND_R19") (pintype "power_in"))
      (node (ref "D4") (pin "R2") (pinfunction "GND_R2") (pintype "power_in"))
      (node (ref "D4") (pin "R29") (pinfunction "GND_R29") (pintype "power_in"))
      (node (ref "D4") (pin "R3") (pinfunction "GND_R3") (pintype "power_in"))
      (node (ref "D4") (pin "R4") (pinfunction "GND_R4") (pintype "power_in"))
      (node (ref "D4") (pin "R6") (pinfunction "GND_R6") (pintype "power_in"))
      (node (ref "D4") (pin "R7") (pinfunction "GND_R7") (pintype "power_in"))
      (node (ref "D4") (pin "R8") (pinfunction "GND_R8") (pintype "power_in"))
      (node (ref "D4") (pin "R9") (pinfunction "GND_R9") (pintype "power_in"))
      (node (ref "D4") (pin "T1") (pinfunction "GND_T1") (pintype "power_in"))
      (node (ref "D4") (pin "T12") (pinfunction "GND_T12") (pintype "power_in"))
      (node (ref "D4") (pin "T14") (pinfunction "GND_T14") (pintype "power_in"))
      (node (ref "D4") (pin "T16") (pinfunction "GND_T16") (pintype "power_in"))
      (node (ref "D4") (pin "T18") (pinfunction "GND_T18") (pintype "power_in"))
      (node (ref "D4") (pin "T2") (pinfunction "GND_T2") (pintype "power_in"))
      (node (ref "D4") (pin "T20") (pinfunction "GND_T20") (pintype "power_in"))
      (node (ref "D4") (pin "T22") (pinfunction "GND_T22") (pintype "power_in"))
      (node (ref "D4") (pin "T5") (pinfunction "GND_T5") (pintype "power_in"))
      (node (ref "D4") (pin "T8") (pinfunction "MSEL0_T8") (pintype "input"))
      (node (ref "D4") (pin "U1") (pinfunction "GND_U1") (pintype "power_in"))
      (node (ref "D4") (pin "U13") (pinfunction "GND_U13") (pintype "power_in"))
      (node (ref "D4") (pin "U15") (pinfunction "GND_U15") (pintype "power_in"))
      (node (ref "D4") (pin "U17") (pinfunction "GND_U17") (pintype "power_in"))
      (node (ref "D4") (pin "U19") (pinfunction "GND_U19") (pintype "power_in"))
      (node (ref "D4") (pin "U2") (pinfunction "GND_U2") (pintype "power_in"))
      (node (ref "D4") (pin "U25") (pinfunction "GND_U25") (pintype "power_in"))
      (node (ref "D4") (pin "U3") (pinfunction "GND_U3") (pintype "power_in"))
      (node (ref "D4") (pin "U4") (pinfunction "GND_U4") (pintype "power_in"))
      (node (ref "D4") (pin "U6") (pinfunction "GND_U6") (pintype "power_in"))
      (node (ref "D4") (pin "V1") (pinfunction "GND_V1") (pintype "power_in"))
      (node (ref "D4") (pin "V14") (pinfunction "GND_V14") (pintype "power_in"))
      (node (ref "D4") (pin "V16") (pinfunction "GND_V16") (pintype "power_in"))
      (node (ref "D4") (pin "V18") (pinfunction "GND_V18") (pintype "power_in"))
      (node (ref "D4") (pin "V2") (pinfunction "GND_V2") (pintype "power_in"))
      (node (ref "D4") (pin "V20") (pinfunction "GND_V20") (pintype "power_in"))
      (node (ref "D4") (pin "V23") (pinfunction "GND_V23") (pintype "power_in"))
      (node (ref "D4") (pin "V28") (pinfunction "GND_V28") (pintype "power_in"))
      (node (ref "D4") (pin "V5") (pinfunction "GND_V5") (pintype "power_in"))
      (node (ref "D4") (pin "V8") (pinfunction "GND_V8") (pintype "power_in"))
      (node (ref "D4") (pin "W1") (pinfunction "GND_W1") (pintype "power_in"))
      (node (ref "D4") (pin "W11") (pinfunction "GND_W11") (pintype "power_in"))
      (node (ref "D4") (pin "W13") (pinfunction "GND_W13") (pintype "power_in"))
      (node (ref "D4") (pin "W15") (pinfunction "GND_W15") (pintype "power_in"))
      (node (ref "D4") (pin "W17") (pinfunction "GND_W17") (pintype "power_in"))
      (node (ref "D4") (pin "W19") (pinfunction "GND_W19") (pintype "power_in"))
      (node (ref "D4") (pin "W2") (pinfunction "GND_W2") (pintype "power_in"))
      (node (ref "D4") (pin "W21") (pinfunction "GND_W21") (pintype "power_in"))
      (node (ref "D4") (pin "W3") (pinfunction "GND_W3") (pintype "power_in"))
      (node (ref "D4") (pin "W4") (pinfunction "GND_W4") (pintype "power_in"))
      (node (ref "D4") (pin "W6") (pinfunction "GND_W6") (pintype "power_in"))
      (node (ref "D4") (pin "W7") (pinfunction "GND_W7") (pintype "power_in"))
      (node (ref "D4") (pin "W8") (pinfunction "GND_W8") (pintype "power_in"))
      (node (ref "D4") (pin "Y1") (pinfunction "GND_Y1") (pintype "power_in"))
      (node (ref "D4") (pin "Y14") (pinfunction "GND_Y14") (pintype "power_in"))
      (node (ref "D4") (pin "Y2") (pinfunction "GND_Y2") (pintype "power_in"))
      (node (ref "D4") (pin "Y24") (pinfunction "GND_Y24") (pintype "power_in"))
      (node (ref "D4") (pin "Y5") (pinfunction "GND_Y5") (pintype "power_in"))
      (node (ref "D4") (pin "Y7") (pinfunction "GND_Y7") (pintype "power_in"))
      (node (ref "R33") (pin "1") (pinfunction "1_1") (pintype "passive"))
      (node (ref "X1") (pin "10") (pintype "passive"))
      (node (ref "X1") (pin "2") (pintype "passive"))
    )
    (net (code "2") (name "/Fpga_CONF_DONE") (class "Default")
      (node (ref "D4") (pin "L8") (pinfunction "CONF_DONE_L8") (pintype "bidirectional"))
      (node (ref "R31") (pin "2") (pinfunction "2_2") (pintype "passive"))
    )
    (net (code "3") (name "/Fpga_DCLK") (class "Default")
      (node (ref "D4") (pin "T7") (pinfunction "DCLK_T7") (pintype "bidirectional"))
      (node (ref "R32") (pin "2") (pinfunction "2_2") (pintype "passive"))
    )
    (net (code "4") (name "/Fpga_Data0") (class "Default")
      (node (ref "D4") (pin "AG5") (pinfunction "AS_DATA0,_ASDO,_DATA0_AG5") (pintype "bidirectional"))
    )
    (net (code "5") (name "/Fpga_nCONFIG") (class "Default")
      (node (ref "D4") (pin "C5") (pinfunction "nCONFIG_C5") (pintype "input"))
      (node (ref "R30") (pin "2") (pinfunction "2_2") (pintype "passive"))
    )
    (net (code "6") (name "/Fpga_nSTATUS") (class "Default")
      (node (ref "D4") (pin "K7") (pinfunction "nSTATUS_K7") (pintype "bidirectional"))
    )
    (net (code "7") (name "/TCK") (class "Default")
      (node (ref "D4") (pin "AC7") (pinfunction "TCK_AC7") (pintype "input"))
      (node (ref "R26") (pin "2") (pinfunction "2_2") (pintype "passive"))
      (node (ref "R33") (pin "2") (pinfunction "2_2") (pintype "passive"))
      (node (ref "X1") (pin "1") (pintype "passive"))
    )
    (net (code "8") (name "/TDI") (class "Default")
      (node (ref "D4") (pin "U7") (pinfunction "TDI_U7") (pintype "input"))
      (node (ref "R27") (pin "1") (pinfunction "1_1") (pintype "passive"))
      (node (ref "X1") (pin "9") (pintype "passive"))
    )
    (net (code "9") (name "/TDO") (class "Default")
      (node (ref "D4") (pin "W9") (pinfunction "TDO_W9") (pintype "output"))
      (node (ref "X1") (pin "3") (pintype "passive"))
    )
    (net (code "10") (name "/TMS") (class "Default")
      (node (ref "D4") (pin "V7") (pinfunction "TMS_V7") (pintype "input"))
      (node (ref "R25") (pin "2") (pinfunction "2_2") (pintype "passive"))
      (node (ref "X1") (pin "5") (pintype "passive"))
    )
    (net (code "11") (name "/v1p1d") (class "Default")
      (node (ref "C63") (pin "2") (pinfunction "2_2") (pintype "passive"))
      (node (ref "C64") (pin "2") (pinfunction "2_2") (pintype "passive"))
      (node (ref "C65") (pin "2") (pinfunction "2_2") (pintype "passive"))
      (node (ref "C66") (pin "2") (pinfunction "2_2") (pintype "passive"))
      (node (ref "C67") (pin "2") (pinfunction "2_2") (pintype "passive"))
      (node (ref "C68") (pin "2") (pinfunction "2_2") (pintype "passive"))
      (node (ref "C69") (pin "2") (pinfunction "2_2") (pintype "passive"))
      (node (ref "C75") (pin "2") (pinfunction "2_2") (pintype "passive"))
      (node (ref "C76") (pin "2") (pinfunction "2_2") (pintype "passive"))
      (node (ref "C77") (pin "2") (pinfunction "2_2") (pintype "passive"))
      (node (ref "C78") (pin "2") (pinfunction "2_2") (pintype "passive"))
      (node (ref "C79") (pin "2") (pinfunction "2_2") (pintype "passive"))
      (node (ref "C80") (pin "2") (pinfunction "2_2") (pintype "passive"))
      (node (ref "C81") (pin "2") (pinfunction "2_2") (pintype "passive"))
      (node (ref "C87") (pin "2") (pinfunction "2_2") (pintype "passive"))
      (node (ref "C88") (pin "2") (pinfunction "2_2") (pintype "passive"))
      (node (ref "C89") (pin "2") (pinfunction "2_2") (pintype "passive"))
      (node (ref "C90") (pin "2") (pinfunction "2_2") (pintype "passive"))
      (node (ref "C91") (pin "2") (pinfunction "2_2") (pintype "passive"))
      (node (ref "C92") (pin "2") (pinfunction "2_2") (pintype "passive"))
      (node (ref "C93") (pin "2") (pinfunction "2_2") (pintype "passive"))
      (node (ref "C94") (pin "2") (pinfunction "2_2") (pintype "passive"))
      (node (ref "D4") (pin "AA5") (pinfunction "VCC_AA5") (pintype "power_in"))
      (node (ref "D4") (pin "AC5") (pinfunction "VCC_AC5") (pintype "power_in"))
      (node (ref "D4") (pin "AD6") (pinfunction "VCC_AD6") (pintype "power_in"))
      (node (ref "D4") (pin "J5") (pinfunction "VCC_J5") (pintype "power_in"))
      (node (ref "D4") (pin "L5") (pinfunction "VCC_L5") (pintype "power_in"))
      (node (ref "D4") (pin "M13") (pinfunction "VCC_M13") (pintype "power_in"))
      (node (ref "D4") (pin "M15") (pinfunction "VCC_M15") (pintype "power_in"))
      (node (ref "D4") (pin "M17") (pinfunction "VCC_M17") (pintype "power_in"))
      (node (ref "D4") (pin "M19") (pinfunction "VCC_M19") (pintype "power_in"))
      (node (ref "D4") (pin "M6") (pinfunction "VCC_M6") (pintype "power_in"))
      (node (ref "D4") (pin "N14") (pinfunction "VCC_N14") (pintype "power_in"))
      (node (ref "D4") (pin "N16") (pinfunction "VCC_N16") (pintype "power_in"))
      (node (ref "D4") (pin "N18") (pinfunction "VCC_N18") (pintype "power_in"))
      (node (ref "D4") (pin "N5") (pinfunction "VCC_N5") (pintype "power_in"))
      (node (ref "D4") (pin "P13") (pinfunction "VCC_P13") (pintype "power_in"))
      (node (ref "D4") (pin "P15") (pinfunction "VCC_P15") (pintype "power_in"))
      (node (ref "D4") (pin "P17") (pinfunction "VCC_P17") (pintype "power_in"))
      (node (ref "D4") (pin "P19") (pinfunction "VCC_P19") (pintype "power_in"))
      (node (ref "D4") (pin "R14") (pinfunction "VCC_R14") (pintype "power_in"))
      (node (ref "D4") (pin "R16") (pinfunction "VCC_R16") (pintype "power_in"))
      (node (ref "D4") (pin "R18") (pinfunction "VCC_R18") (pintype "power_in"))
      (node (ref "D4") (pin "R5") (pinfunction "VCC_R5") (pintype "power_in"))
      (node (ref "D4") (pin "T13") (pinfunction "VCC_T13") (pintype "power_in"))
      (node (ref "D4") (pin "T15") (pinfunction "VCC_T15") (pintype "power_in"))
      (node (ref "D4") (pin "T17") (pinfunction "VCC_T17") (pintype "power_in"))
      (node (ref "D4") (pin "T19") (pinfunction "VCC_T19") (pintype "power_in"))
      (node (ref "D4") (pin "T6") (pinfunction "VCC_T6") (pintype "power_in"))
      (node (ref "D4") (pin "U14") (pinfunction "VCC_U14") (pintype "power_in"))
      (node (ref "D4") (pin "U16") (pinfunction "VCC_U16") (pintype "power_in"))
      (node (ref "D4") (pin "U18") (pinfunction "VCC_U18") (pintype "power_in"))
      (node (ref "D4") (pin "U20") (pinfunction "VCC_U20") (pintype "power_in"))
      (node (ref "D4") (pin "U5") (pinfunction "VCC_U5") (pintype "power_in"))
      (node (ref "D4") (pin "V13") (pinfunction "VCC_V13") (pintype "power_in"))
      (node (ref "D4") (pin "V15") (pinfunction "VCC_V15") (pintype "power_in"))
      (node (ref "D4") (pin "V17") (pinfunction "VCC_V17") (pintype "power_in"))
      (node (ref "D4") (pin "V19") (pinfunction "VCC_V19") (pintype "power_in"))
      (node (ref "D4") (pin "W14") (pinfunction "VCC_W14") (pintype "power_in"))
      (node (ref "D4") (pin "W16") (pinfunction "VCC_W16") (pintype "power_in"))
      (node (ref "D4") (pin "W18") (pinfunction "VCC_W18") (pintype "power_in"))
      (node (ref "D4") (pin "W20") (pinfunction "VCC_W20") (pintype "power_in"))
      (node (ref "D4") (pin "W5") (pinfunction "VCC_W5") (pintype "power_in"))
      (node (ref "D4") (pin "Y6") (pinfunction "VCC_Y6") (pintype "power_in"))
    )
    (net (code "12") (name "/v1p5d") (class "Default")
      (node (ref "C111") (pin "2") (pinfunction "2_2") (pintype "passive"))
      (node (ref "C112") (pin "2") (pinfunction "2_2") (pintype "passive"))
      (node (ref "C113") (pin "2") (pinfunction "2_2") (pintype "passive"))
      (node (ref "C114") (pin "2") (pinfunction "2_2") (pintype "passive"))
      (node (ref "C115") (pin "2") (pinfunction "2_2") (pintype "passive"))
      (node (ref "C116") (pin "2") (pinfunction "2_2") (pintype "passive"))
      (node (ref "C117") (pin "2") (pinfunction "2_2") (pintype "passive"))
      (node (ref "C124") (pin "2") (pinfunction "2_2") (pintype "passive"))
      (node (ref "C125") (pin "2") (pinfunction "2_2") (pintype "passive"))
      (node (ref "C126") (pin "2") (pinfunction "2_2") (pintype "passive"))
      (node (ref "C127") (pin "2") (pinfunction "2_2") (pintype "passive"))
      (node (ref "C128") (pin "2") (pinfunction "2_2") (pintype "passive"))
      (node (ref "C129") (pin "2") (pinfunction "2_2") (pintype "passive"))
      (node (ref "C130") (pin "2") (pinfunction "2_2") (pintype "passive"))
      (node (ref "C135") (pin "2") (pinfunction "2_2") (pintype "passive"))
      (node (ref "C136") (pin "2") (pinfunction "2_2") (pintype "passive"))
      (node (ref "C137") (pin "2") (pinfunction "2_2") (pintype "passive"))
      (node (ref "C138") (pin "2") (pinfunction "2_2") (pintype "passive"))
      (node (ref "C250") (pin "2") (pinfunction "2_2") (pintype "passive"))
      (node (ref "C251") (pin "2") (pinfunction "2_2") (pintype "passive"))
      (node (ref "C252") (pin "2") (pinfunction "2_2") (pintype "passive"))
      (node (ref "C253") (pin "2") (pinfunction "2_2") (pintype "passive"))
      (node (ref "D4") (pin "A22") (pinfunction "VCCIO7A_A22") (pintype "power_in"))
      (node (ref "D4") (pin "A7") (pinfunction "VCCIO8A_A7") (pintype "power_in"))
      (node (ref "D4") (pin "AA12") (pinfunction "VCCIO3B_AA12") (pintype "power_in"))
      (node (ref "D4") (pin "AB15") (pinfunction "VCCIO4A_AB15") (pintype "power_in"))
      (node (ref "D4") (pin "AC18") (pinfunction "VCCIO4A_AC18") (pintype "power_in"))
      (node (ref "D4") (pin "AD21") (pinfunction "VCCIO4A_AD21") (pintype "power_in"))
      (node (ref "D4") (pin "AE14") (pinfunction "VCCIO3B_AE14") (pintype "power_in"))
      (node (ref "D4") (pin "AF17") (pinfunction "VCCIO4A_AF17") (pintype "power_in"))
      (node (ref "D4") (pin "AG10") (pinfunction "VCCIO3B_AG10") (pintype "power_in"))
      (node (ref "D4") (pin "AG20") (pinfunction "VCCIO4A_AG20") (pintype "power_in"))
      (node (ref "D4") (pin "AH13") (pinfunction "VCCIO3B_AH13") (pintype "power_in"))
      (node (ref "D4") (pin "AH23") (pinfunction "VCCIO4A_AH23") (pintype "power_in"))
      (node (ref "D4") (pin "AJ16") (pinfunction "VCCIO4A_AJ16") (pintype "power_in"))
      (node (ref "D4") (pin "AJ26") (pinfunction "VCCIO4A_AJ26") (pintype "power_in"))
      (node (ref "D4") (pin "AK19") (pinfunction "VCCIO4A_AK19") (pintype "power_in"))
      (node (ref "D4") (pin "AK4") (pinfunction "VCCIO3B_AK4") (pintype "power_in"))
      (node (ref "D4") (pin "AK9") (pinfunction "VCCIO3B_AK9") (pintype "power_in"))
      (node (ref "D4") (pin "B15") (pinfunction "VCCIO7A_B15") (pintype "power_in"))
      (node (ref "D4") (pin "B25") (pinfunction "VCCIO7A_B25") (pintype "power_in"))
      (node (ref "D4") (pin "B5") (pinfunction "VCCIO8A_B5") (pintype "power_in"))
      (node (ref "D4") (pin "C18") (pinfunction "VCCIO7A_C18") (pintype "power_in"))
      (node (ref "D4") (pin "C8") (pinfunction "VCCIO8A_C8") (pintype "power_in"))
      (node (ref "D4") (pin "D11") (pinfunction "VCCIO8A_D11") (pintype "power_in"))
      (node (ref "D4") (pin "D21") (pinfunction "VCCIO7A_D21") (pintype "power_in"))
      (node (ref "D4") (pin "E14") (pinfunction "VCCIO8A_E14") (pintype "power_in"))
      (node (ref "D4") (pin "E24") (pinfunction "VCCIO7A_E24") (pintype "power_in"))
      (node (ref "D4") (pin "F17") (pinfunction "VCCIO7A_F17") (pintype "power_in"))
      (node (ref "D4") (pin "F7") (pinfunction "VCCIO8A_F7") (pintype "power_in"))
      (node (ref "D4") (pin "G10") (pinfunction "VCCIO8A_G10") (pintype "power_in"))
      (node (ref "D4") (pin "G20") (pinfunction "VCCIO7A_G20") (pintype "power_in"))
      (node (ref "D4") (pin "H10") (pinfunction "VCCBAT_H10") (pintype "power_in"))
      (node (ref "D4") (pin "H13") (pinfunction "VCCIO8A_H13") (pintype "power_in"))
      (node (ref "D4") (pin "H23") (pinfunction "VCCIO7A_H23") (pintype "power_in"))
      (node (ref "D4") (pin "J16") (pinfunction "VCCIO8A_J16") (pintype "power_in"))
      (node (ref "D4") (pin "K19") (pinfunction "VCCIO7A_K19") (pintype "power_in"))
      (node (ref "D4") (pin "L12") (pinfunction "VCCIO8A_L12") (pintype "power_in"))
      (node (ref "D4") (pin "Y19") (pinfunction "VCCIO4A_Y19") (pintype "power_in"))
    )
    (net (code "13") (name "/v1p8d") (class "Default")
      (node (ref "L5") (pin "2") (pinfunction "2_2") (pintype "passive"))
    )
    (net (code "14") (name "/v2p5d") (class "Default")
      (node (ref "C100") (pin "2") (pinfunction "2_2") (pintype "passive"))
      (node (ref "C101") (pin "2") (pinfunction "2_2") (pintype "passive"))
      (node (ref "C102") (pin "2") (pinfunction "2_2") (pintype "passive"))
      (node (ref "C103") (pin "2") (pinfunction "2_2") (pintype "passive"))
      (node (ref "C104") (pin "2") (pinfunction "2_2") (pintype "passive"))
      (node (ref "C105") (pin "2") (pinfunction "2_2") (pintype "passive"))
      (node (ref "C106") (pin "2") (pinfunction "2_2") (pintype "passive"))
      (node (ref "C107") (pin "2") (pinfunction "2_2") (pintype "passive"))
      (node (ref "C108") (pin "2") (pinfunction "2_2") (pintype "passive"))
      (node (ref "C122") (pin "2") (pinfunction "2_2") (pintype "passive"))
      (node (ref "C123") (pin "2") (pinfunction "2_2") (pintype "passive"))
      (node (ref "C131") (pin "2") (pinfunction "2_2") (pintype "passive"))
      (node (ref "C132") (pin "2") (pinfunction "2_2") (pintype "passive"))
      (node (ref "C133") (pin "2") (pinfunction "2_2") (pintype "passive"))
      (node (ref "C134") (pin "2") (pinfunction "2_2") (pintype "passive"))
      (node (ref "C139") (pin "2") (pinfunction "2_2") (pintype "passive"))
      (node (ref "C140") (pin "2") (pinfunction "2_2") (pintype "passive"))
      (node (ref "C141") (pin "2") (pinfunction "2_2") (pintype "passive"))
      (node (ref "C142") (pin "2") (pinfunction "2_2") (pintype "passive"))
      (node (ref "C97") (pin "2") (pinfunction "2_2") (pintype "passive"))
      (node (ref "C98") (pin "2") (pinfunction "2_2") (pintype "passive"))
      (node (ref "C99") (pin "2") (pinfunction "2_2") (pintype "passive"))
      (node (ref "D4") (pin "AA22") (pinfunction "VCCIO5A_AA22") (pintype "power_in"))
      (node (ref "D4") (pin "AB11") (pinfunction "VCCPD3A_AB11") (pintype "power_in"))
      (node (ref "D4") (pin "AB25") (pinfunction "VCCIO5A_AB25") (pintype "power_in"))
      (node (ref "D4") (pin "AC12") (pinfunction "VCCPD3B4A_AC12") (pintype "power_in"))
      (node (ref "D4") (pin "AC17") (pinfunction "VCCPD3B4A_AC17") (pintype "power_in"))
      (node (ref "D4") (pin "AC20") (pinfunction "VCCPD3B4A_AC20") (pintype "power_in"))
      (node (ref "D4") (pin "AC28") (pinfunction "VCCIO5B_AC28") (pintype "power_in"))
      (node (ref "D4") (pin "AD10") (pinfunction "VCCPD3A_AD10") (pintype "power_in"))
      (node (ref "D4") (pin "AD15") (pinfunction "VCCPD3B4A_AD15") (pintype "power_in"))
      (node (ref "D4") (pin "AE11") (pinfunction "VCCPD3B4A_AE11") (pintype "power_in"))
      (node (ref "D4") (pin "AE21") (pinfunction "VCCPD3B4A_AE21") (pintype "power_in"))
      (node (ref "D4") (pin "AE24") (pinfunction "VCCIO5A_AE24") (pintype "power_in"))
      (node (ref "D4") (pin "AF27") (pinfunction "VCCIO5A_AF27") (pintype "power_in"))
      (node (ref "D4") (pin "AG30") (pinfunction "VCCIO5B_AG30") (pintype "power_in"))
      (node (ref "D4") (pin "C28") (pinfunction "VCCIO6A_C28") (pintype "power_in"))
      (node (ref "D4") (pin "D24") (pinfunction "VCCPD7A8A_D24") (pintype "power_in"))
      (node (ref "D4") (pin "F11") (pinfunction "VCCPD7A8A_F11") (pintype "power_in"))
      (node (ref "D4") (pin "F21") (pinfunction "VCCPD7A8A_F21") (pintype "power_in"))
      (node (ref "D4") (pin "F23") (pinfunction "VCCPD7A8A_F23") (pintype "power_in"))
      (node (ref "D4") (pin "F27") (pinfunction "VCCIO6A_F27") (pintype "power_in"))
      (node (ref "D4") (pin "G13") (pinfunction "VCCPD7A8A_G13") (pintype "power_in"))
      (node (ref "D4") (pin "G16") (pinfunction "VCCPD7A8A_G16") (pintype "power_in"))
      (node (ref "D4") (pin "G19") (pinfunction "VCCPD7A8A_G19") (pintype "power_in"))
      (node (ref "D4") (pin "G30") (pinfunction "VCCIO6A_G30") (pintype "power_in"))
      (node (ref "D4") (pin "J26") (pinfunction "VCCIO6A_J26") (pintype "power_in"))
      (node (ref "D4") (pin "K23") (pinfunction "VCCPD6A_K23") (pintype "power_in"))
      (node (ref "D4") (pin "K29") (pinfunction "VCCIO6A_K29") (pintype "power_in"))
      (node (ref "D4") (pin "L22") (pinfunction "VCCIO6A_L22") (pintype "power_in"))
      (node (ref "D4") (pin "M24") (pinfunction "VCCPD6A_M24") (pintype "power_in"))
      (node (ref "D4") (pin "M25") (pinfunction "VCCIO6A_M25") (pintype "power_in"))
      (node (ref "D4") (pin "N28") (pinfunction "VCCIO6A_N28") (pintype "power_in"))
      (node (ref "D4") (pin "P21") (pinfunction "VCCIO6A_P21") (pintype "power_in"))
      (node (ref "D4") (pin "P24") (pinfunction "VCCPD6A_P24") (pintype "power_in"))
      (node (ref "D4") (pin "R24") (pinfunction "VCCIO6A_R24") (pintype "power_in"))
      (node (ref "D4") (pin "T26") (pinfunction "VCCPD5B_T26") (pintype "power_in"))
      (node (ref "D4") (pin "T27") (pinfunction "VCCIO5B_T27") (pintype "power_in"))
      (node (ref "D4") (pin "U24") (pinfunction "VCCPD5B_U24") (pintype "power_in"))
      (node (ref "D4") (pin "U30") (pinfunction "VCCIO5B_U30") (pintype "power_in"))
      (node (ref "D4") (pin "W23") (pinfunction "VCCPD5A_W23") (pintype "power_in"))
      (node (ref "D4") (pin "W25") (pinfunction "VCCPD5A_W25") (pintype "power_in"))
      (node (ref "D4") (pin "W26") (pinfunction "VCCIO5B_W26") (pintype "power_in"))
      (node (ref "D4") (pin "Y29") (pinfunction "VCCIO5B_Y29") (pintype "power_in"))
      (node (ref "L3") (pin "2") (pinfunction "2_2") (pintype "passive"))
      (node (ref "L4") (pin "2") (pinfunction "2_2") (pintype "passive"))
    )
    (net (code "15") (name "/vRefDDR0") (class "Default")
      (node (ref "C118") (pin "2") (pinfunction "2_2") (pintype "passive"))
      (node (ref "C119") (pin "2") (pinfunction "2_2") (pintype "passive"))
      (node (ref "D4") (pin "AH16") (pinfunction "VREFB4AN0_AH16") (pintype "power_in"))
      (node (ref "D4") (pin "AJ13") (pinfunction "VREFB3BN0_AJ13") (pintype "power_in"))
    )
    (net (code "16") (name "/vRefDDR1") (class "Default")
      (node (ref "C120") (pin "2") (pinfunction "2_2") (pintype "passive"))
      (node (ref "C121") (pin "2") (pinfunction "2_2") (pintype "passive"))
      (node (ref "D4") (pin "B16") (pinfunction "VREFB7AN0_B16") (pintype "power_in"))
      (node (ref "D4") (pin "B9") (pinfunction "VREFB8AN0_B9") (pintype "power_in"))
    )
    (net (code "17") (name "/vcc_aux") (class "Default")
      (node (ref "C82") (pin "2") (pinfunction "2_2") (pintype "passive"))
      (node (ref "C83") (pin "2") (pinfunction "2_2") (pintype "passive"))
      (node (ref "C84") (pin "2") (pinfunction "2_2") (pintype "passive"))
      (node (ref "C85") (pin "2") (pinfunction "2_2") (pintype "passive"))
      (node (ref "C86") (pin "2") (pinfunction "2_2") (pintype "passive"))
      (node (ref "D4") (pin "AC10") (pinfunction "VCC_AUX_AC10") (pintype "power_in"))
      (node (ref "D4") (pin "AC16") (pinfunction "VCC_AUX_AC16") (pintype "power_in"))
      (node (ref "D4") (pin "AD22") (pinfunction "VCC_AUX_AD22") (pintype "power_in"))
      (node (ref "D4") (pin "G11") (pinfunction "VCC_AUX_G11") (pintype "power_in"))
      (node (ref "D4") (pin "H16") (pinfunction "VCC_AUX_H16") (pintype "power_in"))
      (node (ref "D4") (pin "H22") (pinfunction "VCC_AUX_H22") (pintype "power_in"))
      (node (ref "L4") (pin "1") (pinfunction "1_1") (pintype "passive"))
    )
    (net (code "18") (name "/vcc_pll") (class "Default")
      (node (ref "C70") (pin "2") (pinfunction "2_2") (pintype "passive"))
      (node (ref "C71") (pin "2") (pinfunction "2_2") (pintype "passive"))
      (node (ref "C72") (pin "2") (pinfunction "2_2") (pintype "passive"))
      (node (ref "C73") (pin "2") (pinfunction "2_2") (pintype "passive"))
      (node (ref "C74") (pin "2") (pinfunction "2_2") (pintype "passive"))
      (node (ref "D4") (pin "AB23") (pinfunction "VCCA_FPLL_AB23") (pintype "power_in"))
      (node (ref "D4") (pin "AB6") (pinfunction "VCCA_FPLL_AB6") (pintype "power_in"))
      (node (ref "D4") (pin "J24") (pinfunction "VCCA_FPLL_J24") (pintype "power_in"))
      (node (ref "D4") (pin "J8") (pinfunction "VCCA_FPLL_J8") (pintype "power_in"))
      (node (ref "D4") (pin "K6") (pinfunction "VCCA_FPLL_K6") (pintype "power_in"))
      (node (ref "D4") (pin "P6") (pinfunction "VCCA_FPLL_P6") (pintype "power_in"))
      (node (ref "D4") (pin "V6") (pinfunction "VCCA_FPLL_V6") (pintype "power_in"))
      (node (ref "D4") (pin "Y8") (pinfunction "VCCA_FPLL_Y8") (pintype "power_in"))
      (node (ref "L3") (pin "1") (pinfunction "1_1") (pintype "passive"))
    )
    (net (code "19") (name "/vccpgm") (class "Default")
      (node (ref "C109") (pin "2") (pinfunction "2_2") (pintype "passive"))
      (node (ref "C110") (pin "2") (pinfunction "2_2") (pintype "passive"))
      (node (ref "C95") (pin "2") (pinfunction "2_2") (pintype "passive"))
      (node (ref "C96") (pin "2") (pinfunction "2_2") (pintype "passive"))
      (node (ref "D4") (pin "AB24") (pinfunction "VCCPGM_AB24") (pintype "power_in"))
      (node (ref "D4") (pin "AC11") (pinfunction "VCCPGM_AC11") (pintype "power_in"))
      (node (ref "D4") (pin "AC8") (pinfunction "VCCIO3A_AC8") (pintype "power_in"))
      (node (ref "D4") (pin "AD11") (pinfunction "VCCIO3A_AD11") (pintype "power_in"))
      (node (ref "D4") (pin "F10") (pinfunction "VCCPGM_F10") (pintype "power_in"))
      (node (ref "D4") (pin "U10") (pinfunction "VCCIO3A_U10") (pintype "power_in"))
      (node (ref "D4") (pin "Y9") (pinfunction "VCCIO3A_Y9") (pintype "power_in"))
      (node (ref "L5") (pin "1") (pinfunction "1_1") (pintype "passive"))
      (node (ref "R25") (pin "1") (pinfunction "1_1") (pintype "passive"))
      (node (ref "R26") (pin "1") (pinfunction "1_1") (pintype "passive"))
      (node (ref "R27") (pin "2") (pinfunction "2_2") (pintype "passive"))
      (node (ref "R28") (pin "2") (pinfunction "2_2") (pintype "passive"))
      (node (ref "R29") (pin "2") (pinfunction "2_2") (pintype "passive"))
      (node (ref "R30") (pin "1") (pinfunction "1_1") (pintype "passive"))
      (node (ref "R31") (pin "1") (pinfunction "1_1") (pintype "passive"))
      (node (ref "R32") (pin "1") (pinfunction "1_1") (pintype "passive"))
      (node (ref "X1") (pin "4") (pintype "passive"))
    )
    (net (code "20") (name "Net-(D4I-MSEL1)") (class "Default")
      (node (ref "D4") (pin "P9") (pinfunction "MSEL1_P9") (pintype "input"))
      (node (ref "R28") (pin "1") (pinfunction "1_1") (pintype "passive"))
    )
    (net (code "21") (name "Net-(D4I-MSEL4)") (class "Default")
      (node (ref "D4") (pin "M7") (pinfunction "MSEL4_M7") (pintype "input"))
      (node (ref "R29") (pin "1") (pinfunction "1_1") (pintype "passive"))
    )
    (net (code "22") (name "unconnected-(D4I-AS_DATA1,_DATA1-PadAE5)") (class "Default")
      (node (ref "D4") (pin "AE5") (pinfunction "AS_DATA1,_DATA1_AE5") (pintype "bidirectional"))
    )
    (net (code "23") (name "unconnected-(D4I-AS_DATA2,_DATA2-PadAE7)") (class "Default")
      (node (ref "D4") (pin "AE7") (pinfunction "AS_DATA2,_DATA2_AE7") (pintype "bidirectional"))
    )
    (net (code "24") (name "unconnected-(D4I-AS_DATA3,_DATA3-PadAB7)") (class "Default")
      (node (ref "D4") (pin "AB7") (pinfunction "AS_DATA3,_DATA3_AB7") (pintype "bidirectional"))
    )
    (net (code "25") (name "unconnected-(D4I-nCSO,_DATA4-PadAA7)") (class "Default")
      (node (ref "D4") (pin "AA7") (pinfunction "nCSO,_DATA4_AA7") (pintype "output"))
    )
    (net (code "26") (name "unconnected-(X1-Pad6)") (class "Default")
      (node (ref "X1") (pin "6") (pintype "passive"))
    )
    (net (code "27") (name "unconnected-(X1-Pad7)") (class "Default")
      (node (ref "X1") (pin "7") (pintype "passive"))
    )
    (net (code "28") (name "unconnected-(X1-Pad8)") (class "Default")
      (node (ref "X1") (pin "8") (pintype "passive"))
    )
  )
)
